# WaldoRevd.net
KiCad netlist of a schematic drawn in EAGLE
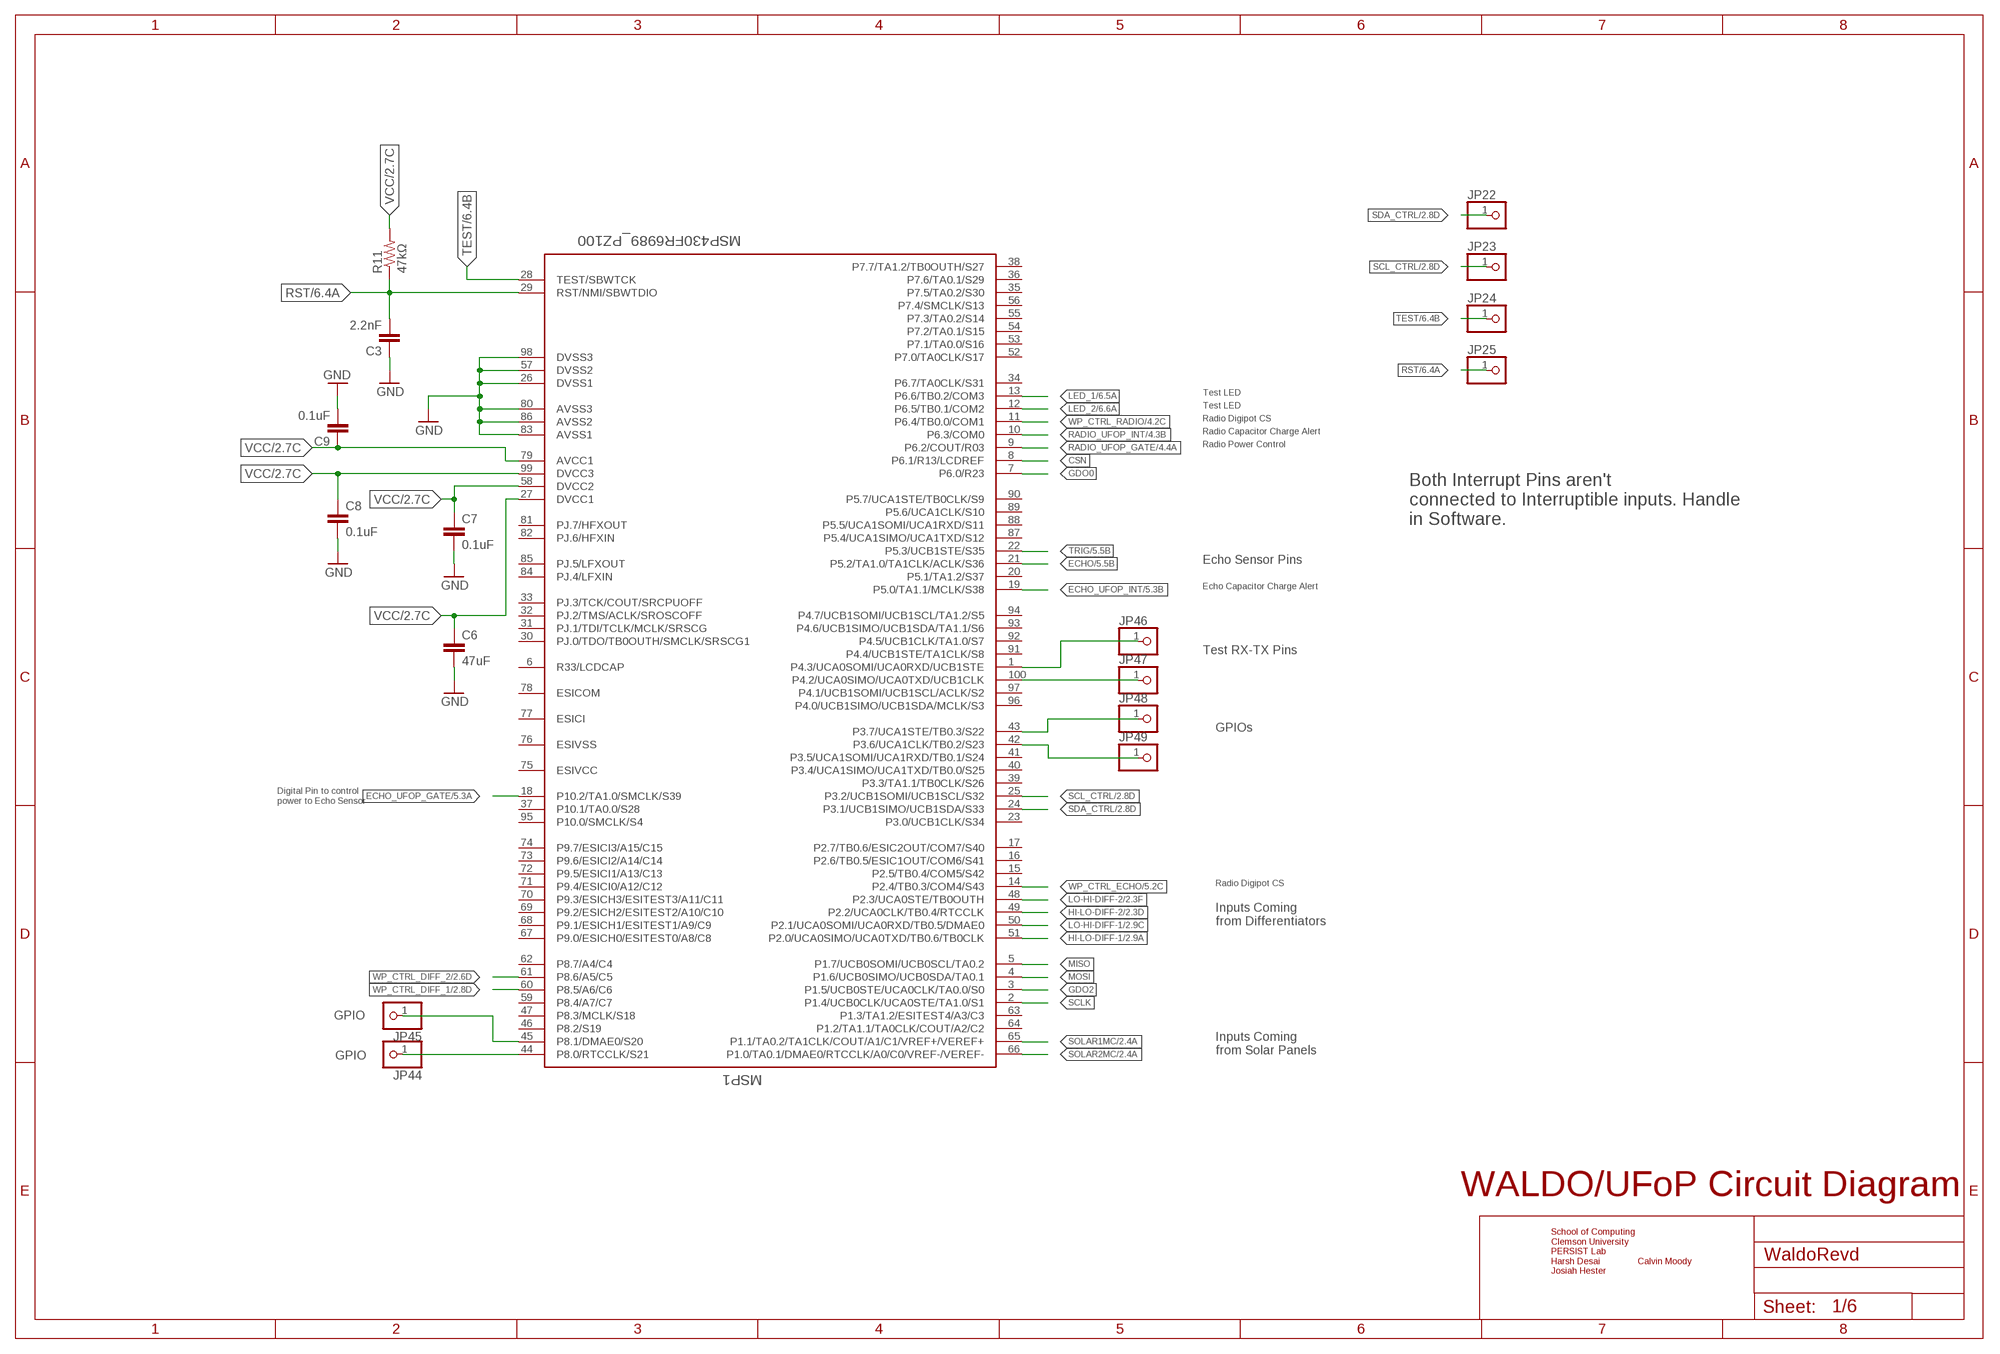
[diagram p0: schematic, sheet 1]
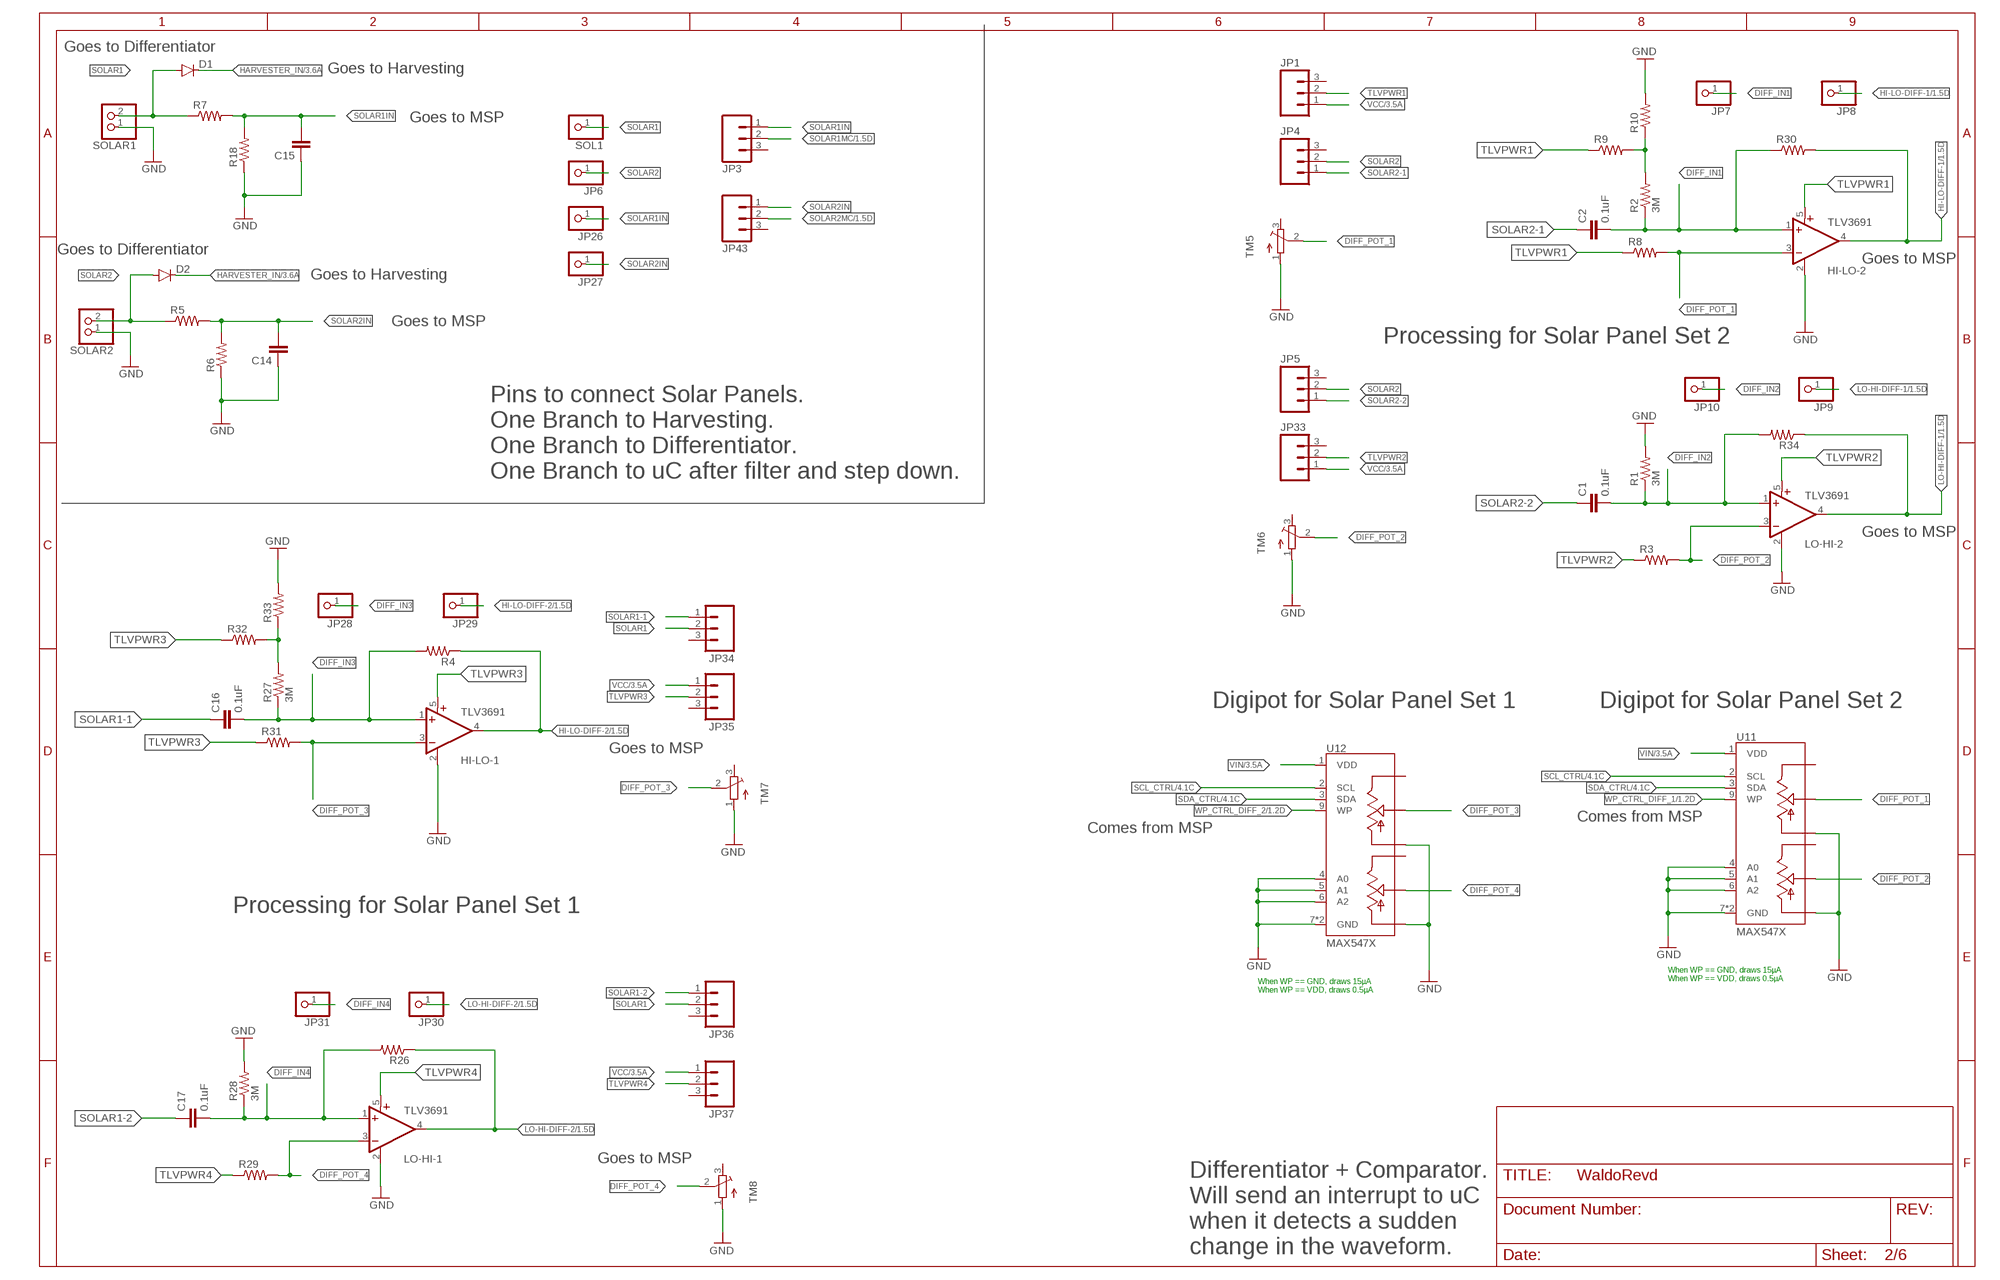
[diagram p1: schematic, sheet 2]
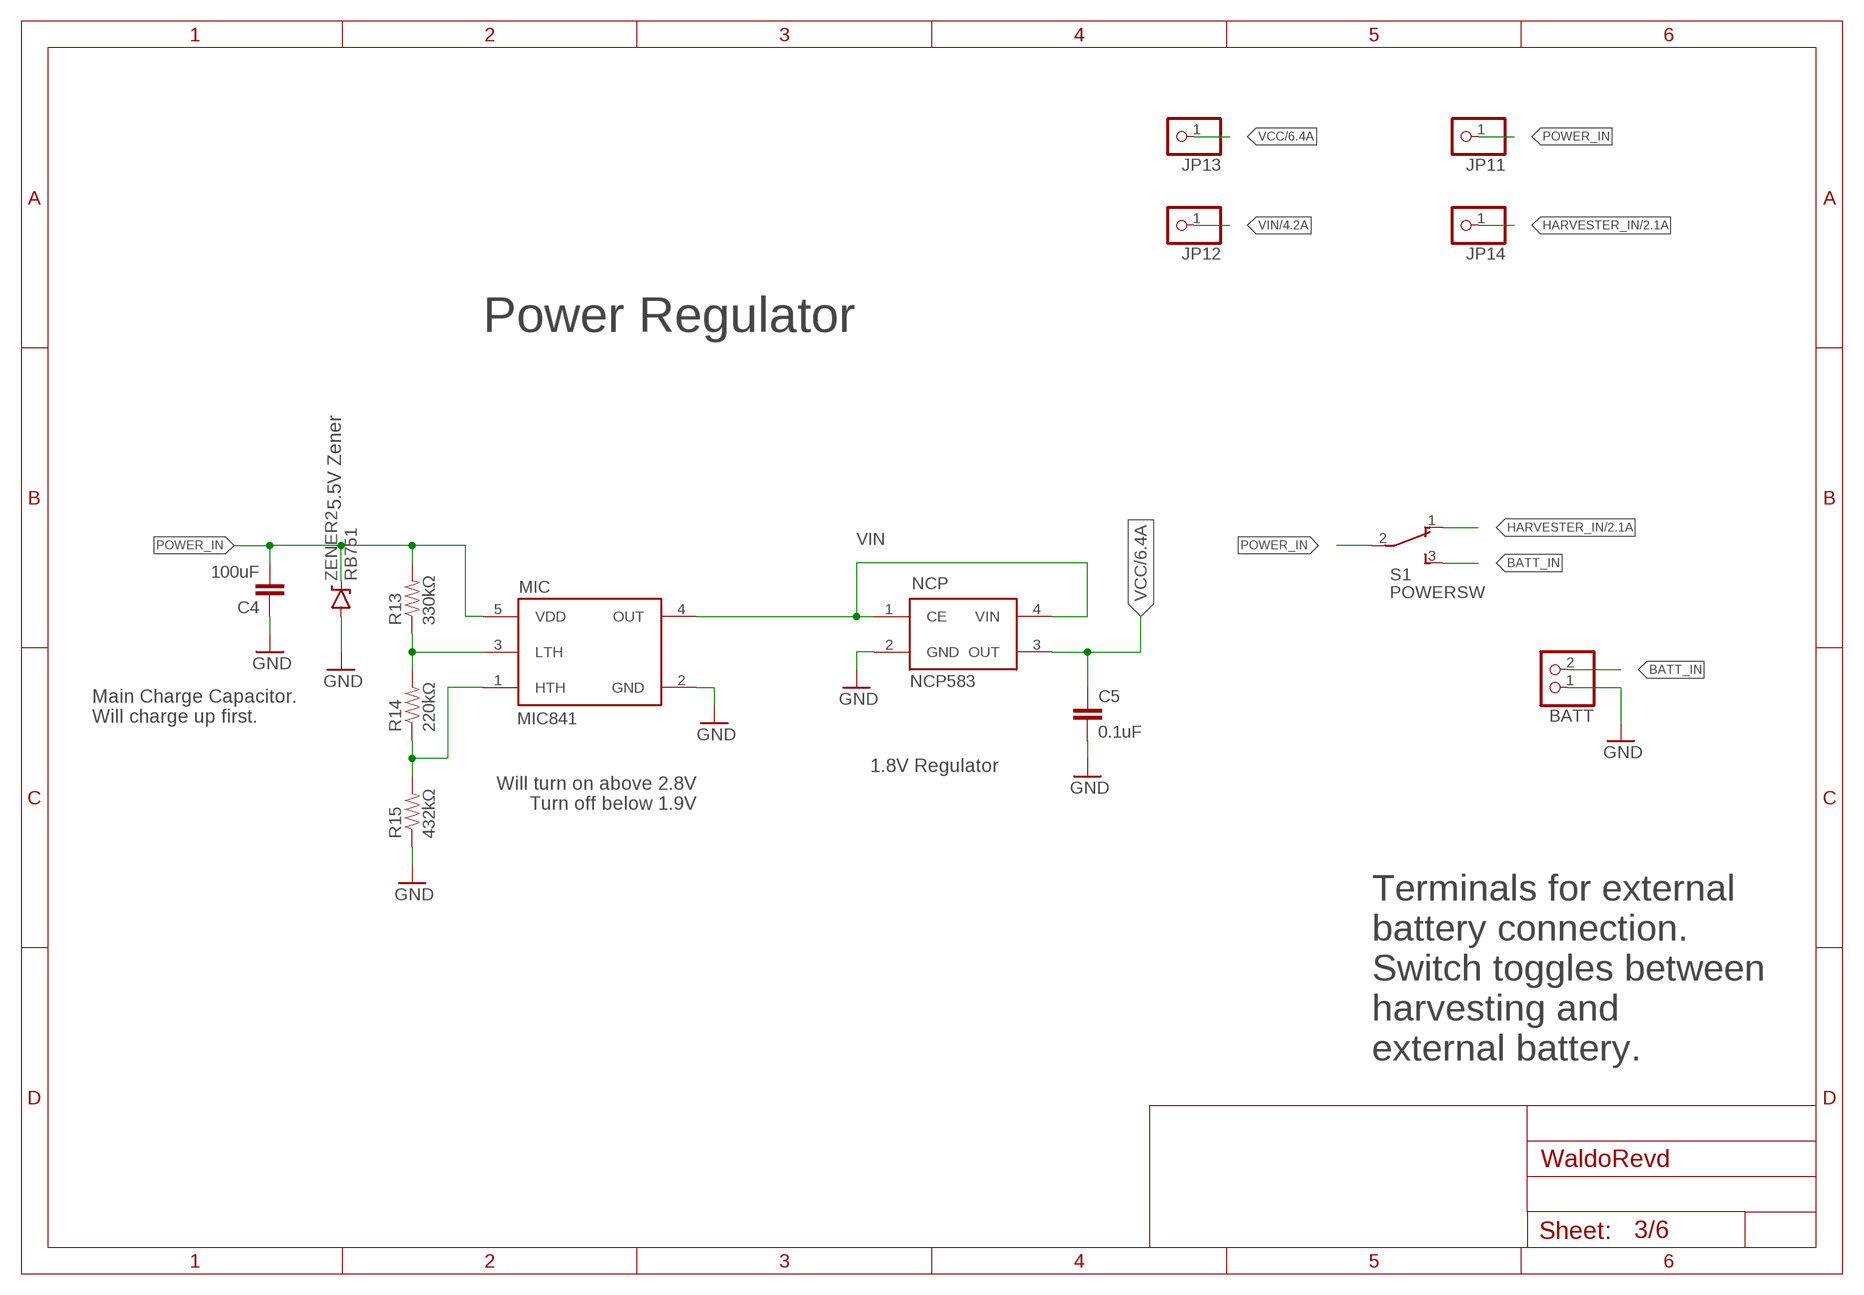
[diagram p2: schematic, sheet 3]
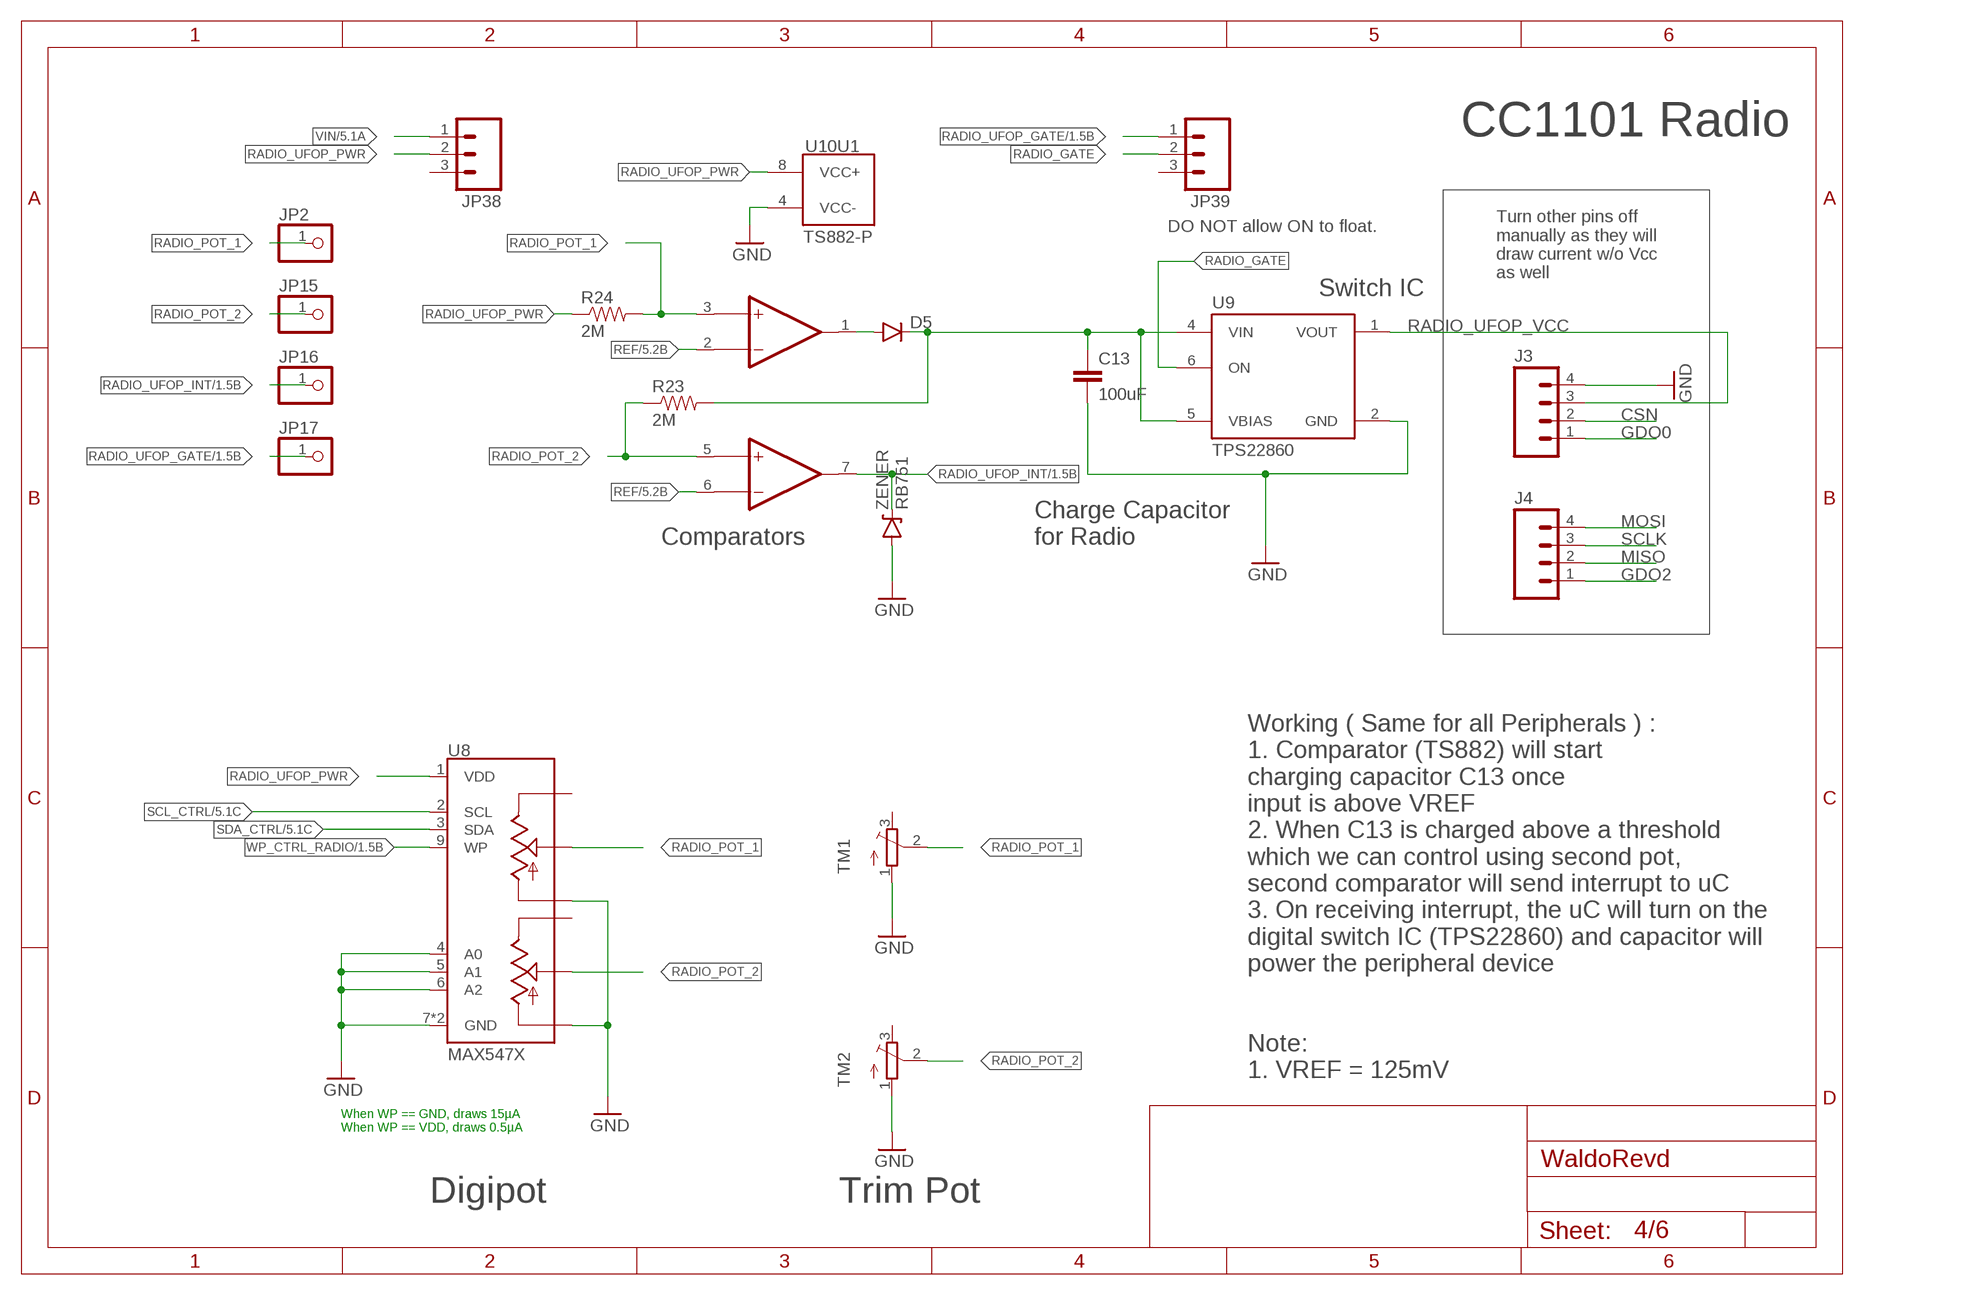
[diagram p3: schematic, sheet 4]
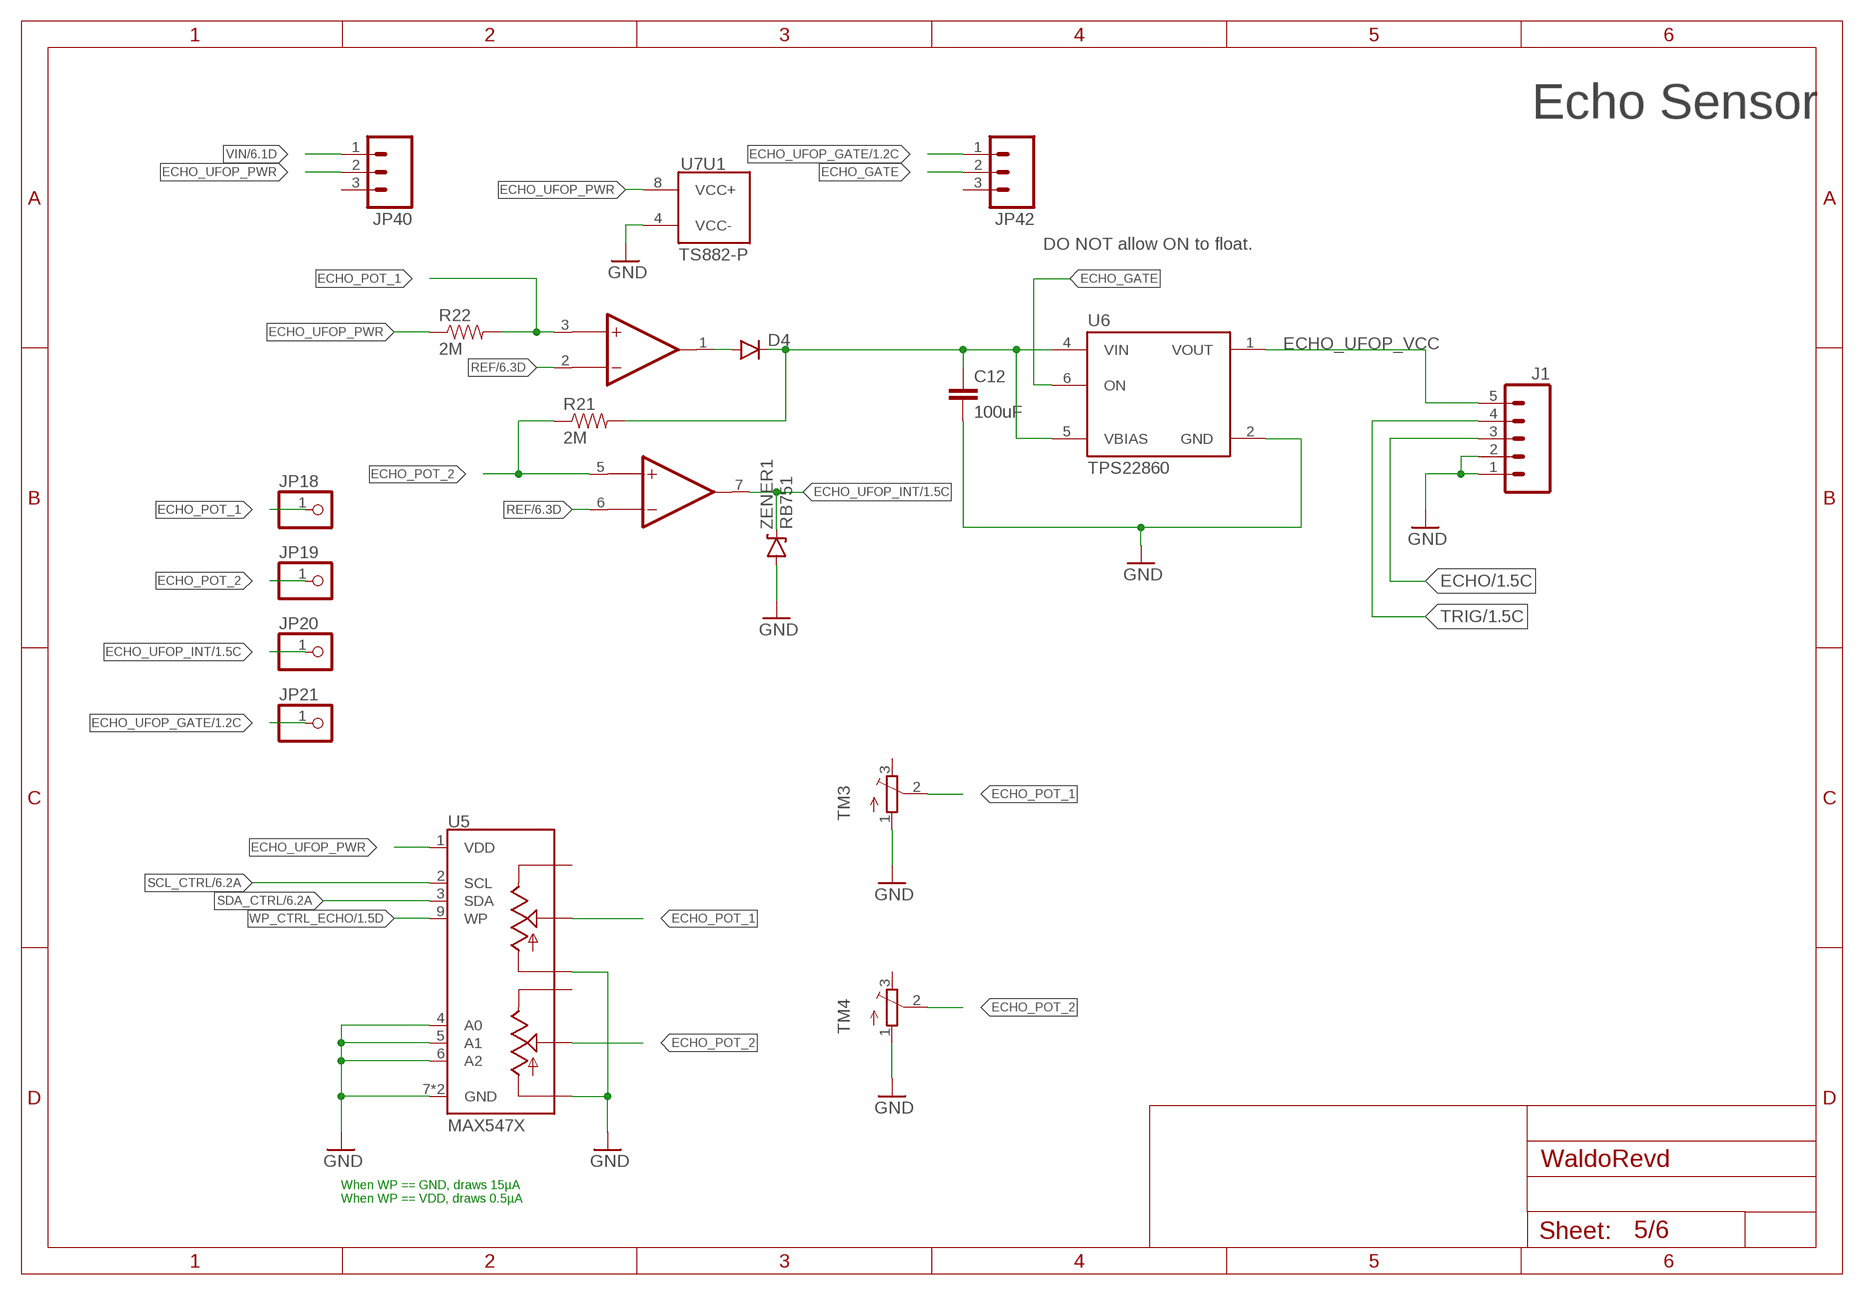
[diagram p4: schematic, sheet 5]
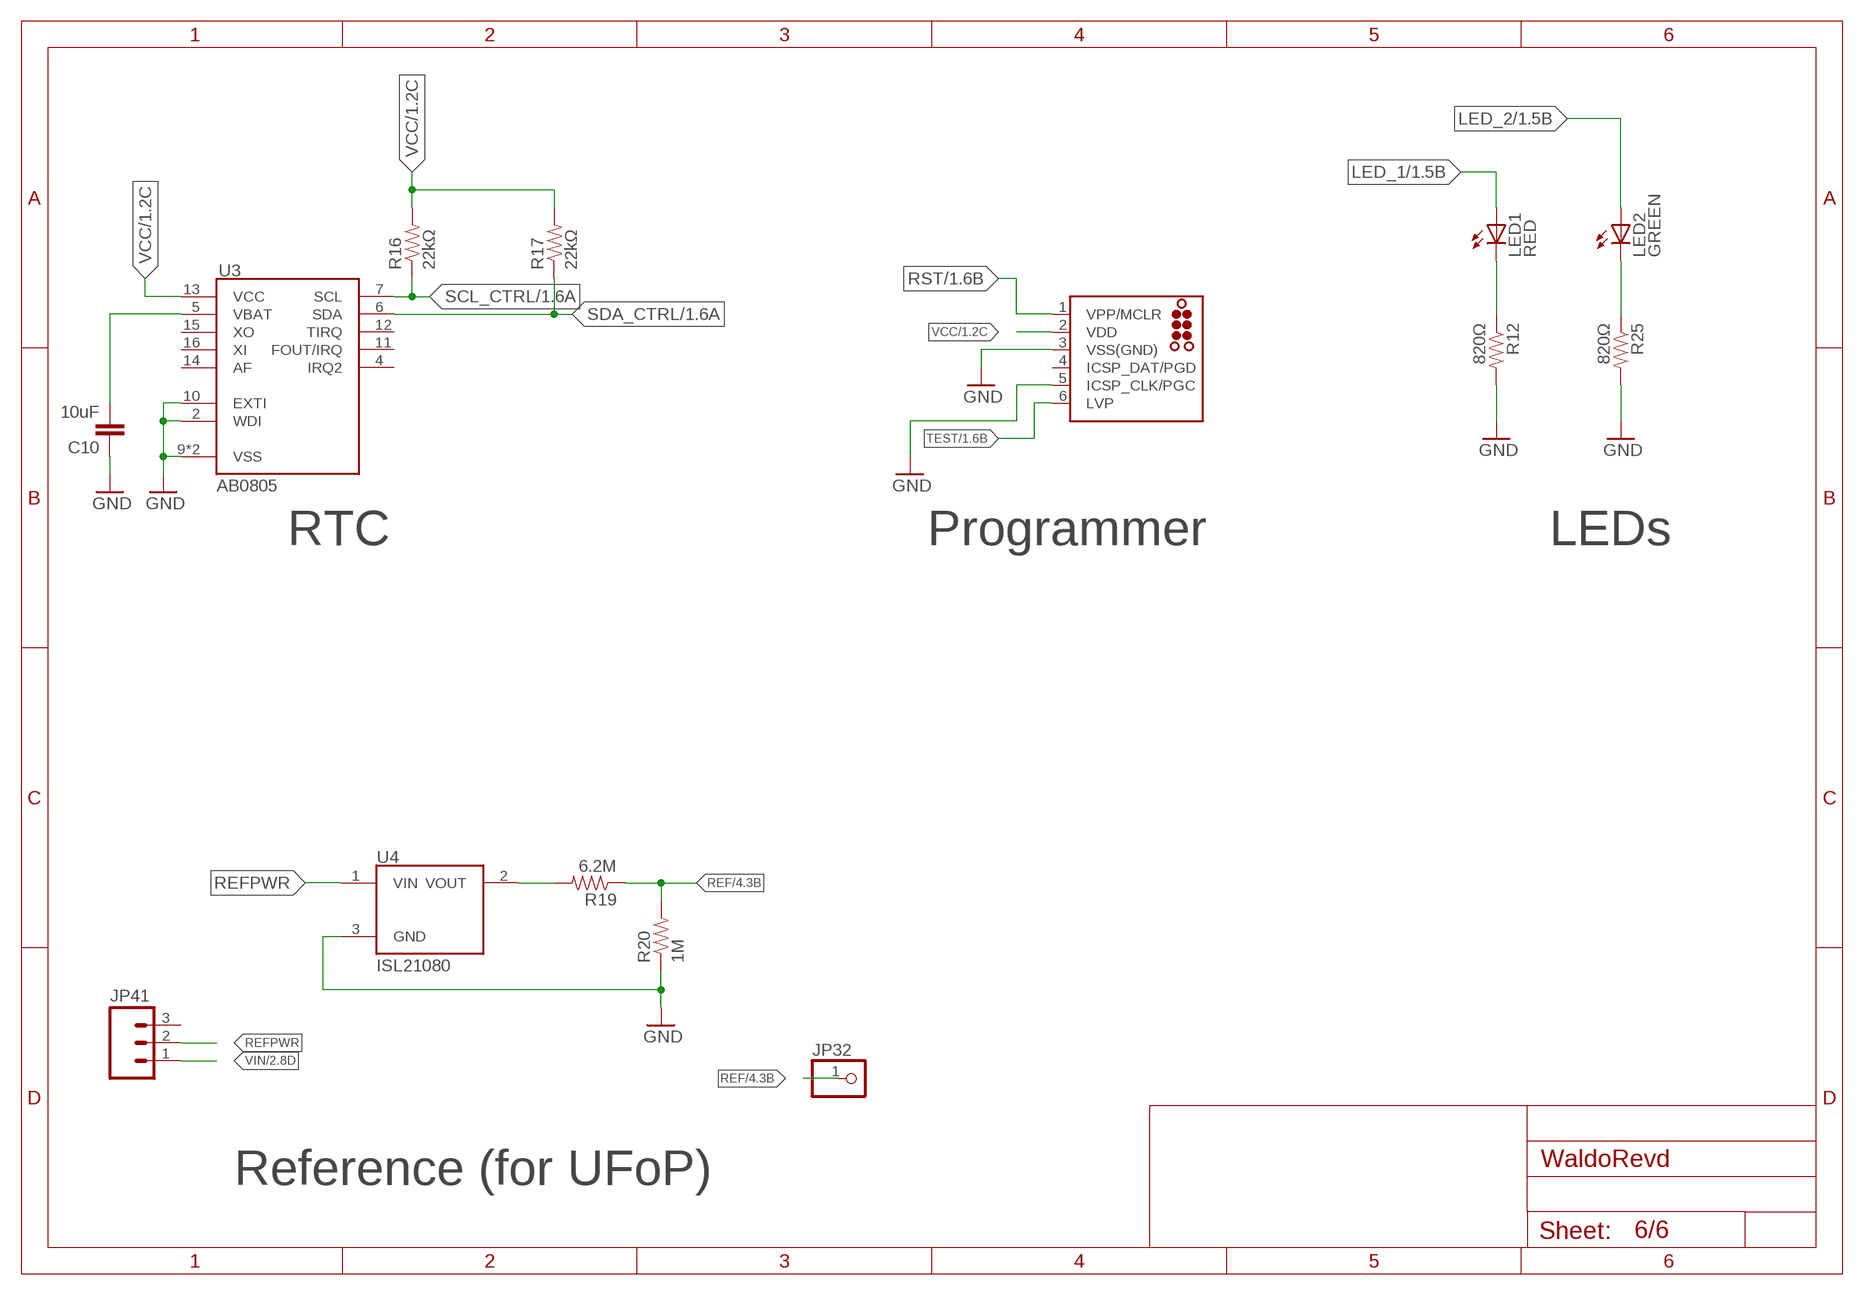
[diagram p5: schematic, sheet 6]

(export (version "E")
  (design (tool "Eeschema 10.0.6"))
  (components
    (comp (ref "C12")
      (value "100uF")
      (footprint "eagle-import:0805")
      (libsource (lib "eagle-import") (part "CAP0805"))
    )
    (comp (ref "D4")
      (value "DIODESOD523")
      (footprint "eagle-import:SOD523")
      (libsource (lib "eagle-import") (part "DIODESOD523"))
    )
    (comp (ref "J1")
      (value "M05PTH")
      (footprint "eagle-import:1X05")
      (libsource (lib "eagle-import") (part "M05PTH"))
    )
    (comp (ref "JP18")
      (value "PINHD-1X1")
      (footprint "eagle-import:1X01")
      (libsource (lib "eagle-import") (part "PINHD-1X1"))
    )
    (comp (ref "JP19")
      (value "PINHD-1X1")
      (footprint "eagle-import:1X01")
      (libsource (lib "eagle-import") (part "PINHD-1X1"))
    )
    (comp (ref "JP20")
      (value "PINHD-1X1")
      (footprint "eagle-import:1X01")
      (libsource (lib "eagle-import") (part "PINHD-1X1"))
    )
    (comp (ref "JP21")
      (value "PINHD-1X1")
      (footprint "eagle-import:1X01")
      (libsource (lib "eagle-import") (part "PINHD-1X1"))
    )
    (comp (ref "JP40")
      (value "M03")
      (footprint "eagle-import:1X03-1.27MM")
      (libsource (lib "eagle-import") (part "M03"))
    )
    (comp (ref "JP42")
      (value "M03")
      (footprint "eagle-import:1X03-1.27MM")
      (libsource (lib "eagle-import") (part "M03"))
    )
    (comp (ref "R21")
      (value "2M")
      (footprint "eagle-import:0805")
      (libsource (lib "eagle-import") (part "RESISTOR0805-RES"))
    )
    (comp (ref "R22")
      (value "2M")
      (footprint "eagle-import:0805")
      (libsource (lib "eagle-import") (part "RESISTOR0805-RES"))
    )
    (comp (ref "TM3")
      (value "TRIMPOTTC33X")
      (footprint "eagle-import:TC33X")
      (libsource (lib "eagle-import") (part "TRIMPOTTC33X"))
    )
    (comp (ref "TM4")
      (value "TRIMPOTTC33X")
      (footprint "eagle-import:TC33X")
      (libsource (lib "eagle-import") (part "TRIMPOTTC33X"))
    )
    (comp (ref "U5")
      (value "MAX547X")
      (footprint "eagle-import:QFN16")
      (libsource (lib "eagle-import") (part "MAX547X"))
    )
    (comp (ref "U6")
      (value "TPS22860")
      (footprint "eagle-import:TSOT23-6")
      (libsource (lib "eagle-import") (part "TPS22860"))
    )
    (comp (ref "U7")
      (value "TS882-P")
      (footprint "eagle-import:UDFN8")
      (fields (field (name "DIGIKEY") "497-14073-1-ND"))
      (libsource (lib "eagle-import") (part "TS882-P"))
    )
    (comp (ref "ZENER1")
      (value "RB751")
      (footprint "eagle-import:SOD-523")
      (libsource (lib "eagle-import") (part "DIODE-ZENER"))
    )
    (comp (ref "C13")
      (value "100uF")
      (footprint "eagle-import:0805")
      (libsource (lib "eagle-import") (part "CAP0805"))
    )
    (comp (ref "D5")
      (value "DIODESOD523")
      (footprint "eagle-import:SOD523")
      (libsource (lib "eagle-import") (part "DIODESOD523"))
    )
    (comp (ref "J3")
      (value "M04PTH")
      (footprint "eagle-import:1X04")
      (libsource (lib "eagle-import") (part "M04PTH"))
    )
    (comp (ref "J4")
      (value "M04PTH")
      (footprint "eagle-import:1X04")
      (libsource (lib "eagle-import") (part "M04PTH"))
    )
    (comp (ref "JP2")
      (value "PINHD-1X1")
      (footprint "eagle-import:1X01")
      (libsource (lib "eagle-import") (part "PINHD-1X1"))
    )
    (comp (ref "JP15")
      (value "PINHD-1X1")
      (footprint "eagle-import:1X01")
      (libsource (lib "eagle-import") (part "PINHD-1X1"))
    )
    (comp (ref "JP16")
      (value "PINHD-1X1")
      (footprint "eagle-import:1X01")
      (libsource (lib "eagle-import") (part "PINHD-1X1"))
    )
    (comp (ref "JP17")
      (value "PINHD-1X1")
      (footprint "eagle-import:1X01")
      (libsource (lib "eagle-import") (part "PINHD-1X1"))
    )
    (comp (ref "JP38")
      (value "M03")
      (footprint "eagle-import:1X03-1.27MM")
      (libsource (lib "eagle-import") (part "M03"))
    )
    (comp (ref "JP39")
      (value "M03")
      (footprint "eagle-import:1X03-1.27MM")
      (libsource (lib "eagle-import") (part "M03"))
    )
    (comp (ref "R23")
      (value "2M")
      (footprint "eagle-import:0805")
      (libsource (lib "eagle-import") (part "RESISTOR0805-RES"))
    )
    (comp (ref "R24")
      (value "2M")
      (footprint "eagle-import:0805")
      (libsource (lib "eagle-import") (part "RESISTOR0805-RES"))
    )
    (comp (ref "TM1")
      (value "TRIMPOTTC33X")
      (footprint "eagle-import:TC33X")
      (libsource (lib "eagle-import") (part "TRIMPOTTC33X"))
    )
    (comp (ref "TM2")
      (value "TRIMPOTTC33X")
      (footprint "eagle-import:TC33X")
      (libsource (lib "eagle-import") (part "TRIMPOTTC33X"))
    )
    (comp (ref "U8")
      (value "MAX547X")
      (footprint "eagle-import:QFN16")
      (libsource (lib "eagle-import") (part "MAX547X"))
    )
    (comp (ref "U9")
      (value "TPS22860")
      (footprint "eagle-import:TSOT23-6")
      (libsource (lib "eagle-import") (part "TPS22860"))
    )
    (comp (ref "U10")
      (value "TS882-P")
      (footprint "eagle-import:UDFN8")
      (fields (field (name "DIGIKEY") "497-14073-1-ND"))
      (libsource (lib "eagle-import") (part "TS882-P"))
    )
    (comp (ref "ZENER")
      (value "RB751")
      (footprint "eagle-import:SOD-523")
      (libsource (lib "eagle-import") (part "DIODE-ZENER"))
    )
    (comp (ref "C3")
      (value "2.2nF")
      (footprint "eagle-import:0805")
      (libsource (lib "eagle-import") (part "CAP0805"))
    )
    (comp (ref "C6")
      (value "47uF")
      (footprint "eagle-import:0805")
      (libsource (lib "eagle-import") (part "CAP0805"))
    )
    (comp (ref "C7")
      (value "0.1uF")
      (footprint "eagle-import:0805")
      (libsource (lib "eagle-import") (part "CAP0805"))
    )
    (comp (ref "C8")
      (value "0.1uF")
      (footprint "eagle-import:0805")
      (libsource (lib "eagle-import") (part "CAP0805"))
    )
    (comp (ref "C9")
      (value "0.1uF")
      (footprint "eagle-import:0805")
      (libsource (lib "eagle-import") (part "CAP0805"))
    )
    (comp (ref "JP22")
      (value "PINHD-1X1")
      (footprint "eagle-import:1X01")
      (libsource (lib "eagle-import") (part "PINHD-1X1"))
    )
    (comp (ref "JP23")
      (value "PINHD-1X1")
      (footprint "eagle-import:1X01")
      (libsource (lib "eagle-import") (part "PINHD-1X1"))
    )
    (comp (ref "JP24")
      (value "PINHD-1X1")
      (footprint "eagle-import:1X01")
      (libsource (lib "eagle-import") (part "PINHD-1X1"))
    )
    (comp (ref "JP25")
      (value "PINHD-1X1")
      (footprint "eagle-import:1X01")
      (libsource (lib "eagle-import") (part "PINHD-1X1"))
    )
    (comp (ref "JP44")
      (value "PINHD-1X1")
      (footprint "eagle-import:1X01")
      (libsource (lib "eagle-import") (part "PINHD-1X1"))
    )
    (comp (ref "JP45")
      (value "PINHD-1X1")
      (footprint "eagle-import:1X01")
      (libsource (lib "eagle-import") (part "PINHD-1X1"))
    )
    (comp (ref "JP46")
      (value "PINHD-1X1")
      (footprint "eagle-import:1X01")
      (libsource (lib "eagle-import") (part "PINHD-1X1"))
    )
    (comp (ref "JP47")
      (value "PINHD-1X1")
      (footprint "eagle-import:1X01")
      (libsource (lib "eagle-import") (part "PINHD-1X1"))
    )
    (comp (ref "JP48")
      (value "PINHD-1X1")
      (footprint "eagle-import:1X01")
      (libsource (lib "eagle-import") (part "PINHD-1X1"))
    )
    (comp (ref "JP49")
      (value "PINHD-1X1")
      (footprint "eagle-import:1X01")
      (libsource (lib "eagle-import") (part "PINHD-1X1"))
    )
    (comp (ref "MSP1")
      (value "MSP430FR6989_PZ100")
      (footprint "eagle-import:PZ100")
      (libsource (lib "eagle-import") (part "MSP430FR6989_PZ100"))
    )
    (comp (ref "R11")
      (value "47kΩ")
      (footprint "eagle-import:0805")
      (libsource (lib "eagle-import") (part "RESISTOR0805-RES"))
    )
    (comp (ref "C10")
      (value "10uF")
      (footprint "eagle-import:0805")
      (libsource (lib "eagle-import") (part "CAP0805"))
    )
    (comp (ref "J2")
      (value "TC2030-MCP-NL")
      (footprint "eagle-import:TC2030-MCP-NL")
      (libsource (lib "eagle-import") (part "TC2030-MCP-NL"))
    )
    (comp (ref "JP32")
      (value "PINHD-1X1")
      (footprint "eagle-import:1X01")
      (libsource (lib "eagle-import") (part "PINHD-1X1"))
    )
    (comp (ref "JP41")
      (value "M03")
      (footprint "eagle-import:1X03-1.27MM")
      (libsource (lib "eagle-import") (part "M03"))
    )
    (comp (ref "LED1")
      (value "RED")
      (footprint "eagle-import:CHIP-LED0805")
      (libsource (lib "eagle-import") (part "LEDCHIP-LED0805"))
    )
    (comp (ref "LED2")
      (value "GREEN")
      (footprint "eagle-import:CHIP-LED0805")
      (libsource (lib "eagle-import") (part "LEDCHIP-LED0805"))
    )
    (comp (ref "R12")
      (value "820Ω")
      (footprint "eagle-import:0805")
      (libsource (lib "eagle-import") (part "RESISTOR0805-RES"))
    )
    (comp (ref "R16")
      (value "22kΩ")
      (footprint "eagle-import:0805")
      (libsource (lib "eagle-import") (part "RESISTOR0805-RES"))
    )
    (comp (ref "R17")
      (value "22kΩ")
      (footprint "eagle-import:0805")
      (libsource (lib "eagle-import") (part "RESISTOR0805-RES"))
    )
    (comp (ref "R19")
      (value "6.2M")
      (footprint "eagle-import:0805")
      (libsource (lib "eagle-import") (part "RESISTOR0805-RES"))
    )
    (comp (ref "R20")
      (value "1M")
      (footprint "eagle-import:0805")
      (libsource (lib "eagle-import") (part "RESISTOR0805-RES"))
    )
    (comp (ref "R25")
      (value "820Ω")
      (footprint "eagle-import:0805")
      (libsource (lib "eagle-import") (part "RESISTOR0805-RES"))
    )
    (comp (ref "U3")
      (value "AB0805")
      (footprint "eagle-import:QFN16")
      (libsource (lib "eagle-import") (part "AB0805"))
    )
    (comp (ref "U4")
      (value "ISL21080")
      (footprint "eagle-import:SOT-23")
      (libsource (lib "eagle-import") (part "ISL21080"))
    )
    (comp (ref "C1")
      (value "0.1uF")
      (footprint "eagle-import:0805")
      (libsource (lib "eagle-import") (part "CAP0805"))
    )
    (comp (ref "C2")
      (value "0.1uF")
      (footprint "eagle-import:0805")
      (libsource (lib "eagle-import") (part "CAP0805"))
    )
    (comp (ref "C14")
      (value "CAP0805")
      (footprint "eagle-import:0805")
      (libsource (lib "eagle-import") (part "CAP0805"))
    )
    (comp (ref "C15")
      (value "CAP0805")
      (footprint "eagle-import:0805")
      (libsource (lib "eagle-import") (part "CAP0805"))
    )
    (comp (ref "C16")
      (value "0.1uF")
      (footprint "eagle-import:0805")
      (libsource (lib "eagle-import") (part "CAP0805"))
    )
    (comp (ref "C17")
      (value "0.1uF")
      (footprint "eagle-import:0805")
      (libsource (lib "eagle-import") (part "CAP0805"))
    )
    (comp (ref "D1")
      (value "DIODESOD523")
      (footprint "eagle-import:SOD523")
      (libsource (lib "eagle-import") (part "DIODESOD523"))
    )
    (comp (ref "D2")
      (value "DIODESOD523")
      (footprint "eagle-import:SOD523")
      (libsource (lib "eagle-import") (part "DIODESOD523"))
    )
    (comp (ref "HI-LO-1")
      (value "TLV3691")
      (footprint "eagle-import:SC70-5")
      (libsource (lib "eagle-import") (part "TLV3691"))
    )
    (comp (ref "HI-LO-2")
      (value "TLV3691")
      (footprint "eagle-import:SC70-5")
      (libsource (lib "eagle-import") (part "TLV3691"))
    )
    (comp (ref "JP1")
      (value "M03")
      (footprint "eagle-import:1X03-1.27MM")
      (libsource (lib "eagle-import") (part "M03"))
    )
    (comp (ref "JP3")
      (value "M03")
      (footprint "eagle-import:1X03-1.27MM")
      (libsource (lib "eagle-import") (part "M03"))
    )
    (comp (ref "JP4")
      (value "M03")
      (footprint "eagle-import:1X03-1.27MM")
      (libsource (lib "eagle-import") (part "M03"))
    )
    (comp (ref "JP5")
      (value "M03")
      (footprint "eagle-import:1X03-1.27MM")
      (libsource (lib "eagle-import") (part "M03"))
    )
    (comp (ref "JP6")
      (value "PINHD-1X1")
      (footprint "eagle-import:1X01")
      (libsource (lib "eagle-import") (part "PINHD-1X1"))
    )
    (comp (ref "JP7")
      (value "PINHD-1X1")
      (footprint "eagle-import:1X01")
      (libsource (lib "eagle-import") (part "PINHD-1X1"))
    )
    (comp (ref "JP8")
      (value "PINHD-1X1")
      (footprint "eagle-import:1X01")
      (libsource (lib "eagle-import") (part "PINHD-1X1"))
    )
    (comp (ref "JP9")
      (value "PINHD-1X1")
      (footprint "eagle-import:1X01")
      (libsource (lib "eagle-import") (part "PINHD-1X1"))
    )
    (comp (ref "JP10")
      (value "PINHD-1X1")
      (footprint "eagle-import:1X01")
      (libsource (lib "eagle-import") (part "PINHD-1X1"))
    )
    (comp (ref "JP26")
      (value "PINHD-1X1")
      (footprint "eagle-import:1X01")
      (libsource (lib "eagle-import") (part "PINHD-1X1"))
    )
    (comp (ref "JP27")
      (value "PINHD-1X1")
      (footprint "eagle-import:1X01")
      (libsource (lib "eagle-import") (part "PINHD-1X1"))
    )
    (comp (ref "JP28")
      (value "PINHD-1X1")
      (footprint "eagle-import:1X01")
      (libsource (lib "eagle-import") (part "PINHD-1X1"))
    )
    (comp (ref "JP29")
      (value "PINHD-1X1")
      (footprint "eagle-import:1X01")
      (libsource (lib "eagle-import") (part "PINHD-1X1"))
    )
    (comp (ref "JP30")
      (value "PINHD-1X1")
      (footprint "eagle-import:1X01")
      (libsource (lib "eagle-import") (part "PINHD-1X1"))
    )
    (comp (ref "JP31")
      (value "PINHD-1X1")
      (footprint "eagle-import:1X01")
      (libsource (lib "eagle-import") (part "PINHD-1X1"))
    )
    (comp (ref "JP33")
      (value "M03")
      (footprint "eagle-import:1X03-1.27MM")
      (libsource (lib "eagle-import") (part "M03"))
    )
    (comp (ref "JP34")
      (value "M03")
      (footprint "eagle-import:1X03-1.27MM")
      (libsource (lib "eagle-import") (part "M03"))
    )
    (comp (ref "JP35")
      (value "M03")
      (footprint "eagle-import:1X03-1.27MM")
      (libsource (lib "eagle-import") (part "M03"))
    )
    (comp (ref "JP36")
      (value "M03")
      (footprint "eagle-import:1X03-1.27MM")
      (libsource (lib "eagle-import") (part "M03"))
    )
    (comp (ref "JP37")
      (value "M03")
      (footprint "eagle-import:1X03-1.27MM")
      (libsource (lib "eagle-import") (part "M03"))
    )
    (comp (ref "JP43")
      (value "M03")
      (footprint "eagle-import:1X03-1.27MM")
      (libsource (lib "eagle-import") (part "M03"))
    )
    (comp (ref "LO-HI-1")
      (value "TLV3691")
      (footprint "eagle-import:SC70-5")
      (libsource (lib "eagle-import") (part "TLV3691"))
    )
    (comp (ref "LO-HI-2")
      (value "TLV3691")
      (footprint "eagle-import:SC70-5")
      (libsource (lib "eagle-import") (part "TLV3691"))
    )
    (comp (ref "R1")
      (value "3M")
      (footprint "eagle-import:0805")
      (libsource (lib "eagle-import") (part "RESISTOR0805-RES"))
    )
    (comp (ref "R2")
      (value "3M")
      (footprint "eagle-import:0805")
      (libsource (lib "eagle-import") (part "RESISTOR0805-RES"))
    )
    (comp (ref "R3")
      (value "RESISTOR0805-RES")
      (footprint "eagle-import:0805")
      (libsource (lib "eagle-import") (part "RESISTOR0805-RES"))
    )
    (comp (ref "R4")
      (value "RESISTOR0805-RES")
      (footprint "eagle-import:0805")
      (libsource (lib "eagle-import") (part "RESISTOR0805-RES"))
    )
    (comp (ref "R5")
      (value "RESISTOR0805-RES")
      (footprint "eagle-import:0805")
      (libsource (lib "eagle-import") (part "RESISTOR0805-RES"))
    )
    (comp (ref "R6")
      (value "RESISTOR0805-RES")
      (footprint "eagle-import:0805")
      (libsource (lib "eagle-import") (part "RESISTOR0805-RES"))
    )
    (comp (ref "R7")
      (value "RESISTOR0805-RES")
      (footprint "eagle-import:0805")
      (libsource (lib "eagle-import") (part "RESISTOR0805-RES"))
    )
    (comp (ref "R8")
      (value "RESISTOR0805-RES")
      (footprint "eagle-import:0805")
      (libsource (lib "eagle-import") (part "RESISTOR0805-RES"))
    )
    (comp (ref "R9")
      (value "RESISTOR0805-RES")
      (footprint "eagle-import:0805")
      (libsource (lib "eagle-import") (part "RESISTOR0805-RES"))
    )
    (comp (ref "R10")
      (value "RESISTOR0805-RES")
      (footprint "eagle-import:0805")
      (libsource (lib "eagle-import") (part "RESISTOR0805-RES"))
    )
    (comp (ref "R18")
      (value "RESISTOR0805-RES")
      (footprint "eagle-import:0805")
      (libsource (lib "eagle-import") (part "RESISTOR0805-RES"))
    )
    (comp (ref "R26")
      (value "RESISTOR0805-RES")
      (footprint "eagle-import:0805")
      (libsource (lib "eagle-import") (part "RESISTOR0805-RES"))
    )
    (comp (ref "R27")
      (value "3M")
      (footprint "eagle-import:0805")
      (libsource (lib "eagle-import") (part "RESISTOR0805-RES"))
    )
    (comp (ref "R28")
      (value "3M")
      (footprint "eagle-import:0805")
      (libsource (lib "eagle-import") (part "RESISTOR0805-RES"))
    )
    (comp (ref "R29")
      (value "RESISTOR0805-RES")
      (footprint "eagle-import:0805")
      (libsource (lib "eagle-import") (part "RESISTOR0805-RES"))
    )
    (comp (ref "R30")
      (value "RESISTOR0805-RES")
      (footprint "eagle-import:0805")
      (libsource (lib "eagle-import") (part "RESISTOR0805-RES"))
    )
    (comp (ref "R31")
      (value "RESISTOR0805-RES")
      (footprint "eagle-import:0805")
      (libsource (lib "eagle-import") (part "RESISTOR0805-RES"))
    )
    (comp (ref "R32")
      (value "RESISTOR0805-RES")
      (footprint "eagle-import:0805")
      (libsource (lib "eagle-import") (part "RESISTOR0805-RES"))
    )
    (comp (ref "R33")
      (value "RESISTOR0805-RES")
      (footprint "eagle-import:0805")
      (libsource (lib "eagle-import") (part "RESISTOR0805-RES"))
    )
    (comp (ref "R34")
      (value "RESISTOR0805-RES")
      (footprint "eagle-import:0805")
      (libsource (lib "eagle-import") (part "RESISTOR0805-RES"))
    )
    (comp (ref "SOL1")
      (value "PINHD-1X1")
      (footprint "eagle-import:1X01")
      (libsource (lib "eagle-import") (part "PINHD-1X1"))
    )
    (comp (ref "SOLAR1")
      (value "PINHD-1X2")
      (footprint "eagle-import:1X02")
      (libsource (lib "eagle-import") (part "PINHD-1X2"))
    )
    (comp (ref "SOLAR2")
      (value "PINHD-1X2")
      (footprint "eagle-import:1X02")
      (libsource (lib "eagle-import") (part "PINHD-1X2"))
    )
    (comp (ref "TM5")
      (value "TRIMPOTTC33X")
      (footprint "eagle-import:TC33X")
      (libsource (lib "eagle-import") (part "TRIMPOTTC33X"))
    )
    (comp (ref "TM6")
      (value "TRIMPOTTC33X")
      (footprint "eagle-import:TC33X")
      (libsource (lib "eagle-import") (part "TRIMPOTTC33X"))
    )
    (comp (ref "TM7")
      (value "TRIMPOTTC33X")
      (footprint "eagle-import:TC33X")
      (libsource (lib "eagle-import") (part "TRIMPOTTC33X"))
    )
    (comp (ref "TM8")
      (value "TRIMPOTTC33X")
      (footprint "eagle-import:TC33X")
      (libsource (lib "eagle-import") (part "TRIMPOTTC33X"))
    )
    (comp (ref "U11")
      (value "MAX547X")
      (footprint "eagle-import:QFN16")
      (libsource (lib "eagle-import") (part "MAX547X"))
    )
    (comp (ref "U12")
      (value "MAX547X")
      (footprint "eagle-import:QFN16")
      (libsource (lib "eagle-import") (part "MAX547X"))
    )
    (comp (ref "BATT")
      (value "PINHD-1X2")
      (footprint "eagle-import:1X02")
      (libsource (lib "eagle-import") (part "PINHD-1X2"))
    )
    (comp (ref "C4")
      (value "100uF")
      (footprint "eagle-import:0805")
      (libsource (lib "eagle-import") (part "CAP0805"))
    )
    (comp (ref "C5")
      (value "0.1uF")
      (footprint "eagle-import:0805")
      (libsource (lib "eagle-import") (part "CAP0805"))
    )
    (comp (ref "JP11")
      (value "PINHD-1X1")
      (footprint "eagle-import:1X01")
      (libsource (lib "eagle-import") (part "PINHD-1X1"))
    )
    (comp (ref "JP12")
      (value "PINHD-1X1")
      (footprint "eagle-import:1X01")
      (libsource (lib "eagle-import") (part "PINHD-1X1"))
    )
    (comp (ref "JP13")
      (value "PINHD-1X1")
      (footprint "eagle-import:1X01")
      (libsource (lib "eagle-import") (part "PINHD-1X1"))
    )
    (comp (ref "JP14")
      (value "PINHD-1X1")
      (footprint "eagle-import:1X01")
      (libsource (lib "eagle-import") (part "PINHD-1X1"))
    )
    (comp (ref "MIC")
      (value "MIC841")
      (footprint "eagle-import:SC70-5")
      (libsource (lib "eagle-import") (part "MIC841"))
    )
    (comp (ref "NCP")
      (value "NCP583")
      (footprint "eagle-import:SC82-AB_1PRIMARY")
      (libsource (lib "eagle-import") (part "NCP583"))
    )
    (comp (ref "R13")
      (value "330kΩ")
      (footprint "eagle-import:0805")
      (libsource (lib "eagle-import") (part "RESISTOR0805-RES"))
    )
    (comp (ref "R14")
      (value "220kΩ")
      (footprint "eagle-import:0805")
      (libsource (lib "eagle-import") (part "RESISTOR0805-RES"))
    )
    (comp (ref "R15")
      (value "432kΩ")
      (footprint "eagle-import:0805")
      (libsource (lib "eagle-import") (part "RESISTOR0805-RES"))
    )
    (comp (ref "S1")
      (value "POWERSW")
      (footprint "eagle-import:TL3XYO")
      (libsource (lib "eagle-import") (part "POWERSW"))
    )
    (comp (ref "ZENER2")
      (value "RB751")
      (footprint "eagle-import:SOD-523")
      (libsource (lib "eagle-import") (part "DIODE-ZENER"))
    )
  )
  (nets
    (net (code "1") (name "BATT_IN") (class "Default")
      (node (ref "BATT") (pin "2") (pinfunction "2_2") (pintype "passive"))
      (node (ref "S1") (pin "3") (pinfunction "S_3") (pintype "passive"))
    )
    (net (code "2") (name "CSN") (class "Default")
      (node (ref "J3") (pin "2") (pinfunction "2_2") (pintype "passive"))
      (node (ref "MSP1") (pin "8") (pinfunction "P6.1/R13/LCDREF_8") (pintype "bidirectional"))
    )
    (net (code "3") (name "DIFF_IN1") (class "Default")
      (node (ref "C2") (pin "2") (pinfunction "2_2") (pintype "passive"))
      (node (ref "HI-LO-2") (pin "1") (pinfunction "+IN_1") (pintype "input"))
      (node (ref "JP7") (pin "1") (pinfunction "1_1") (pintype "passive"))
      (node (ref "R2") (pin "1") (pinfunction "1_1") (pintype "passive"))
      (node (ref "R30") (pin "1") (pinfunction "1_1") (pintype "passive"))
    )
    (net (code "4") (name "DIFF_IN2") (class "Default")
      (node (ref "C1") (pin "2") (pinfunction "2_2") (pintype "passive"))
      (node (ref "JP10") (pin "1") (pinfunction "1_1") (pintype "passive"))
      (node (ref "LO-HI-2") (pin "1") (pinfunction "+IN_1") (pintype "input"))
      (node (ref "R1") (pin "1") (pinfunction "1_1") (pintype "passive"))
      (node (ref "R34") (pin "2") (pinfunction "2_2") (pintype "passive"))
    )
    (net (code "5") (name "DIFF_IN3") (class "Default")
      (node (ref "C16") (pin "2") (pinfunction "2_2") (pintype "passive"))
      (node (ref "HI-LO-1") (pin "1") (pinfunction "+IN_1") (pintype "input"))
      (node (ref "JP28") (pin "1") (pinfunction "1_1") (pintype "passive"))
      (node (ref "R27") (pin "1") (pinfunction "1_1") (pintype "passive"))
      (node (ref "R4") (pin "2") (pinfunction "2_2") (pintype "passive"))
    )
    (net (code "6") (name "DIFF_IN4") (class "Default")
      (node (ref "C17") (pin "2") (pinfunction "2_2") (pintype "passive"))
      (node (ref "JP31") (pin "1") (pinfunction "1_1") (pintype "passive"))
      (node (ref "LO-HI-1") (pin "1") (pinfunction "+IN_1") (pintype "input"))
      (node (ref "R26") (pin "2") (pinfunction "2_2") (pintype "passive"))
      (node (ref "R28") (pin "1") (pinfunction "1_1") (pintype "passive"))
    )
    (net (code "7") (name "DIFF_POT_1") (class "Default")
      (node (ref "HI-LO-2") (pin "3") (pinfunction "-IN_3") (pintype "input"))
      (node (ref "R8") (pin "2") (pinfunction "2_2") (pintype "passive"))
      (node (ref "TM5") (pin "2") (pinfunction "S_2") (pintype "passive"))
      (node (ref "U11") (pin "14") (pinfunction "WA_14") (pintype "passive"))
    )
    (net (code "8") (name "DIFF_POT_2") (class "Default")
      (node (ref "LO-HI-2") (pin "3") (pinfunction "-IN_3") (pintype "input"))
      (node (ref "R3") (pin "2") (pinfunction "2_2") (pintype "passive"))
      (node (ref "TM6") (pin "2") (pinfunction "S_2") (pintype "passive"))
      (node (ref "U11") (pin "11") (pinfunction "WB_11") (pintype "bidirectional"))
    )
    (net (code "9") (name "DIFF_POT_3") (class "Default")
      (node (ref "HI-LO-1") (pin "3") (pinfunction "-IN_3") (pintype "input"))
      (node (ref "R31") (pin "2") (pinfunction "2_2") (pintype "passive"))
      (node (ref "TM7") (pin "2") (pinfunction "S_2") (pintype "passive"))
      (node (ref "U12") (pin "14") (pinfunction "WA_14") (pintype "passive"))
    )
    (net (code "10") (name "DIFF_POT_4") (class "Default")
      (node (ref "LO-HI-1") (pin "3") (pinfunction "-IN_3") (pintype "input"))
      (node (ref "R29") (pin "2") (pinfunction "2_2") (pintype "passive"))
      (node (ref "TM8") (pin "2") (pinfunction "S_2") (pintype "passive"))
      (node (ref "U12") (pin "11") (pinfunction "WB_11") (pintype "bidirectional"))
    )
    (net (code "11") (name "ECHO") (class "Default")
      (node (ref "J1") (pin "3") (pinfunction "3_3") (pintype "passive"))
      (node (ref "MSP1") (pin "21") (pinfunction "P5.2/TA1.0/TA1CLK/ACLK/S36_21") (pintype "bidirectional"))
    )
    (net (code "12") (name "ECHO_GATE") (class "Default")
      (node (ref "JP42") (pin "2") (pinfunction "2_2") (pintype "passive"))
      (node (ref "U6") (pin "6") (pinfunction "ON_6") (pintype "bidirectional"))
    )
    (net (code "13") (name "ECHO_POT_1") (class "Default")
      (node (ref "JP18") (pin "1") (pinfunction "1_1") (pintype "passive"))
      (node (ref "R22") (pin "2") (pinfunction "2_2") (pintype "passive"))
      (node (ref "TM3") (pin "2") (pinfunction "S_2") (pintype "passive"))
      (node (ref "U5") (pin "14") (pinfunction "WA_14") (pintype "passive"))
      (node (ref "U7") (pin "3") (pinfunction "IN1+_3") (pintype "input"))
    )
    (net (code "14") (name "ECHO_POT_2") (class "Default")
      (node (ref "JP19") (pin "1") (pinfunction "1_1") (pintype "passive"))
      (node (ref "R21") (pin "1") (pinfunction "1_1") (pintype "passive"))
      (node (ref "TM4") (pin "2") (pinfunction "S_2") (pintype "passive"))
      (node (ref "U5") (pin "11") (pinfunction "WB_11") (pintype "bidirectional"))
      (node (ref "U7") (pin "5") (pinfunction "IN1+_5") (pintype "input"))
    )
    (net (code "15") (name "ECHO_UFOP_GATE") (class "Default")
      (node (ref "JP21") (pin "1") (pinfunction "1_1") (pintype "passive"))
      (node (ref "JP42") (pin "1") (pinfunction "1_1") (pintype "passive"))
      (node (ref "MSP1") (pin "18") (pinfunction "P10.2/TA1.0/SMCLK/S39_18") (pintype "bidirectional"))
    )
    (net (code "16") (name "ECHO_UFOP_INT") (class "Default")
      (node (ref "JP20") (pin "1") (pinfunction "1_1") (pintype "passive"))
      (node (ref "MSP1") (pin "19") (pinfunction "P5.0/TA1.1/MCLK/S38_19") (pintype "bidirectional"))
      (node (ref "U7") (pin "7") (pinfunction "OUT1_7") (pintype "output"))
      (node (ref "ZENER1") (pin "CATHODE") (pinfunction "C_CATHODE") (pintype "passive"))
    )
    (net (code "17") (name "ECHO_UFOP_PWR") (class "Default")
      (node (ref "JP40") (pin "2") (pinfunction "2_2") (pintype "passive"))
      (node (ref "R22") (pin "1") (pinfunction "1_1") (pintype "passive"))
      (node (ref "U5") (pin "1") (pinfunction "VDD_1") (pintype "bidirectional"))
      (node (ref "U7") (pin "8") (pinfunction "VCC+_8") (pintype "bidirectional"))
    )
    (net (code "18") (name "ECHO_UFOP_VCC") (class "Default")
      (node (ref "J1") (pin "5") (pinfunction "5_5") (pintype "passive"))
      (node (ref "U6") (pin "1") (pinfunction "VOUT_1") (pintype "bidirectional"))
    )
    (net (code "19") (name "GDO0") (class "Default")
      (node (ref "J3") (pin "1") (pinfunction "1_1") (pintype "passive"))
      (node (ref "MSP1") (pin "7") (pinfunction "P6.0/R23_7") (pintype "bidirectional"))
    )
    (net (code "20") (name "GDO2") (class "Default")
      (node (ref "J4") (pin "1") (pinfunction "1_1") (pintype "passive"))
      (node (ref "MSP1") (pin "3") (pinfunction "P1.5/UCB0STE/UCA0CLK/TA0.0/S0_3") (pintype "bidirectional"))
    )
    (net (code "21") (name "GND") (class "Default")
      (node (ref "BATT") (pin "1") (pinfunction "1_1") (pintype "passive"))
      (node (ref "C10") (pin "1") (pinfunction "1_1") (pintype "passive"))
      (node (ref "C12") (pin "2") (pinfunction "2_2") (pintype "passive"))
      (node (ref "C13") (pin "2") (pinfunction "2_2") (pintype "passive"))
      (node (ref "C14") (pin "1") (pinfunction "1_1") (pintype "passive"))
      (node (ref "C15") (pin "1") (pinfunction "1_1") (pintype "passive"))
      (node (ref "C3") (pin "1") (pinfunction "1_1") (pintype "passive"))
      (node (ref "C4") (pin "1") (pinfunction "1_1") (pintype "passive"))
      (node (ref "C5") (pin "2") (pinfunction "2_2") (pintype "passive"))
      (node (ref "C6") (pin "2") (pinfunction "2_2") (pintype "passive"))
      (node (ref "C7") (pin "2") (pinfunction "2_2") (pintype "passive"))
      (node (ref "C8") (pin "2") (pinfunction "2_2") (pintype "passive"))
      (node (ref "C9") (pin "2") (pinfunction "2_2") (pintype "passive"))
      (node (ref "HI-LO-1") (pin "2") (pinfunction "GND_2") (pintype "power_in"))
      (node (ref "HI-LO-2") (pin "2") (pinfunction "GND_2") (pintype "power_in"))
      (node (ref "J1") (pin "1") (pinfunction "1_1") (pintype "passive"))
      (node (ref "J1") (pin "2") (pinfunction "2_2") (pintype "passive"))
      (node (ref "J2") (pin "3") (pinfunction "VSS(GND)_3") (pintype "power_in"))
      (node (ref "J2") (pin "5") (pinfunction "ICSP_CLK/PGC_5") (pintype "output"))
      (node (ref "J3") (pin "4") (pinfunction "4_4") (pintype "passive"))
      (node (ref "LO-HI-1") (pin "2") (pinfunction "GND_2") (pintype "power_in"))
      (node (ref "LO-HI-2") (pin "2") (pinfunction "GND_2") (pintype "power_in"))
      (node (ref "MIC") (pin "2") (pinfunction "GND_2") (pintype "bidirectional"))
      (node (ref "MSP1") (pin "26") (pinfunction "DVSS1_26") (pintype "bidirectional"))
      (node (ref "MSP1") (pin "57") (pinfunction "DVSS2_57") (pintype "bidirectional"))
      (node (ref "MSP1") (pin "80") (pinfunction "AVSS3_80") (pintype "bidirectional"))
      (node (ref "MSP1") (pin "83") (pinfunction "AVSS1_83") (pintype "bidirectional"))
      (node (ref "MSP1") (pin "86") (pinfunction "AVSS2_86") (pintype "bidirectional"))
      (node (ref "MSP1") (pin "98") (pinfunction "DVSS3_98") (pintype "bidirectional"))
      (node (ref "NCP") (pin "2") (pinfunction "GND_2") (pintype "bidirectional"))
      (node (ref "R1") (pin "2") (pinfunction "2_2") (pintype "passive"))
      (node (ref "R10") (pin "2") (pinfunction "2_2") (pintype "passive"))
      (node (ref "R12") (pin "2") (pinfunction "2_2") (pintype "passive"))
      (node (ref "R15") (pin "1") (pinfunction "1_1") (pintype "passive"))
      (node (ref "R18") (pin "1") (pinfunction "1_1") (pintype "passive"))
      (node (ref "R20") (pin "1") (pinfunction "1_1") (pintype "passive"))
      (node (ref "R25") (pin "2") (pinfunction "2_2") (pintype "passive"))
      (node (ref "R28") (pin "2") (pinfunction "2_2") (pintype "passive"))
      (node (ref "R33") (pin "2") (pinfunction "2_2") (pintype "passive"))
      (node (ref "R6") (pin "1") (pinfunction "1_1") (pintype "passive"))
      (node (ref "SOLAR1") (pin "1") (pinfunction "1_1") (pintype "passive"))
      (node (ref "SOLAR2") (pin "1") (pinfunction "1_1") (pintype "passive"))
      (node (ref "TM1") (pin "1") (pinfunction "A_1") (pintype "passive"))
      (node (ref "TM2") (pin "1") (pinfunction "A_1") (pintype "passive"))
      (node (ref "TM3") (pin "1") (pinfunction "A_1") (pintype "passive"))
      (node (ref "TM4") (pin "1") (pinfunction "A_1") (pintype "passive"))
      (node (ref "TM5") (pin "1") (pinfunction "A_1") (pintype "passive"))
      (node (ref "TM6") (pin "1") (pinfunction "A_1") (pintype "passive"))
      (node (ref "TM7") (pin "1") (pinfunction "A_1") (pintype "passive"))
      (node (ref "TM8") (pin "1") (pinfunction "A_1") (pintype "passive"))
      (node (ref "U10") (pin "4") (pinfunction "VCC-_4") (pintype "bidirectional"))
      (node (ref "U11") (pin "10") (pinfunction "LB_10") (pintype "bidirectional"))
      (node (ref "U11") (pin "13") (pinfunction "LA_13") (pintype "passive"))
      (node (ref "U11") (pin "4") (pinfunction "A0_4") (pintype "bidirectional"))
      (node (ref "U11") (pin "5") (pinfunction "A1_5") (pintype "bidirectional"))
      (node (ref "U11") (pin "6") (pinfunction "A2_6") (pintype "bidirectional"))
      (node (ref "U11") (pin "7") (pinfunction "GND_7") (pintype "bidirectional"))
      (node (ref "U11") (pin "TH") (pinfunction "GND_TH") (pintype "bidirectional"))
      (node (ref "U12") (pin "10") (pinfunction "LB_10") (pintype "bidirectional"))
      (node (ref "U12") (pin "13") (pinfunction "LA_13") (pintype "passive"))
      (node (ref "U12") (pin "4") (pinfunction "A0_4") (pintype "bidirectional"))
      (node (ref "U12") (pin "5") (pinfunction "A1_5") (pintype "bidirectional"))
      (node (ref "U12") (pin "6") (pinfunction "A2_6") (pintype "bidirectional"))
      (node (ref "U12") (pin "7") (pinfunction "GND_7") (pintype "bidirectional"))
      (node (ref "U12") (pin "TH") (pinfunction "GND_TH") (pintype "bidirectional"))
      (node (ref "U3") (pin "10") (pinfunction "EXTI_10") (pintype "bidirectional"))
      (node (ref "U3") (pin "2") (pinfunction "WDI_2") (pintype "bidirectional"))
      (node (ref "U3") (pin "9") (pinfunction "VSS_9") (pintype "bidirectional"))
      (node (ref "U3") (pin "TH") (pinfunction "VSS_TH") (pintype "bidirectional"))
      (node (ref "U4") (pin "3") (pinfunction "GND_3") (pintype "bidirectional"))
      (node (ref "U5") (pin "10") (pinfunction "LB_10") (pintype "bidirectional"))
      (node (ref "U5") (pin "13") (pinfunction "LA_13") (pintype "passive"))
      (node (ref "U5") (pin "4") (pinfunction "A0_4") (pintype "bidirectional"))
      (node (ref "U5") (pin "5") (pinfunction "A1_5") (pintype "bidirectional"))
      (node (ref "U5") (pin "6") (pinfunction "A2_6") (pintype "bidirectional"))
      (node (ref "U5") (pin "7") (pinfunction "GND_7") (pintype "bidirectional"))
      (node (ref "U5") (pin "TH") (pinfunction "GND_TH") (pintype "bidirectional"))
      (node (ref "U6") (pin "2") (pinfunction "GND_2") (pintype "bidirectional"))
      (node (ref "U7") (pin "4") (pinfunction "VCC-_4") (pintype "bidirectional"))
      (node (ref "U8") (pin "10") (pinfunction "LB_10") (pintype "bidirectional"))
      (node (ref "U8") (pin "13") (pinfunction "LA_13") (pintype "passive"))
      (node (ref "U8") (pin "4") (pinfunction "A0_4") (pintype "bidirectional"))
      (node (ref "U8") (pin "5") (pinfunction "A1_5") (pintype "bidirectional"))
      (node (ref "U8") (pin "6") (pinfunction "A2_6") (pintype "bidirectional"))
      (node (ref "U8") (pin "7") (pinfunction "GND_7") (pintype "bidirectional"))
      (node (ref "U8") (pin "TH") (pinfunction "GND_TH") (pintype "bidirectional"))
      (node (ref "U9") (pin "2") (pinfunction "GND_2") (pintype "bidirectional"))
      (node (ref "ZENER") (pin "ANODE") (pinfunction "A_ANODE") (pintype "passive"))
      (node (ref "ZENER1") (pin "ANODE") (pinfunction "A_ANODE") (pintype "passive"))
      (node (ref "ZENER2") (pin "ANODE") (pinfunction "A_ANODE") (pintype "passive"))
    )
    (net (code "22") (name "HARVESTER_IN") (class "Default")
      (node (ref "D1") (pin "C") (pinfunction "C_C") (pintype "passive"))
      (node (ref "D2") (pin "C") (pinfunction "C_C") (pintype "passive"))
      (node (ref "JP14") (pin "1") (pinfunction "1_1") (pintype "passive"))
      (node (ref "S1") (pin "1") (pinfunction "O_1") (pintype "passive"))
    )
    (net (code "23") (name "HI-LO-DIFF-1") (class "Default")
      (node (ref "HI-LO-2") (pin "4") (pinfunction "OUT_4") (pintype "output"))
      (node (ref "JP8") (pin "1") (pinfunction "1_1") (pintype "passive"))
      (node (ref "MSP1") (pin "51") (pinfunction "P2.0/UCA0SIMO/UCA0TXD/TB0.6/TB0CLK_51") (pintype "bidirectional"))
      (node (ref "R30") (pin "2") (pinfunction "2_2") (pintype "passive"))
    )
    (net (code "24") (name "HI-LO-DIFF-2") (class "Default")
      (node (ref "HI-LO-1") (pin "4") (pinfunction "OUT_4") (pintype "output"))
      (node (ref "JP29") (pin "1") (pinfunction "1_1") (pintype "passive"))
      (node (ref "MSP1") (pin "49") (pinfunction "P2.2/UCA0CLK/TB0.4/RTCCLK_49") (pintype "bidirectional"))
      (node (ref "R4") (pin "1") (pinfunction "1_1") (pintype "passive"))
    )
    (net (code "25") (name "LED_1") (class "Default")
      (node (ref "LED1") (pin "A") (pinfunction "A_A") (pintype "passive"))
      (node (ref "MSP1") (pin "13") (pinfunction "P6.6/TB0.2/COM3_13") (pintype "bidirectional"))
    )
    (net (code "26") (name "LED_2") (class "Default")
      (node (ref "LED2") (pin "A") (pinfunction "A_A") (pintype "passive"))
      (node (ref "MSP1") (pin "12") (pinfunction "P6.5/TB0.1/COM2_12") (pintype "bidirectional"))
    )
    (net (code "27") (name "LO-HI-DIFF-1") (class "Default")
      (node (ref "JP9") (pin "1") (pinfunction "1_1") (pintype "passive"))
      (node (ref "LO-HI-2") (pin "4") (pinfunction "OUT_4") (pintype "output"))
      (node (ref "MSP1") (pin "50") (pinfunction "P2.1/UCA0SOMI/UCA0RXD/TB0.5/DMAE0_50") (pintype "bidirectional"))
      (node (ref "R34") (pin "1") (pinfunction "1_1") (pintype "passive"))
    )
    (net (code "28") (name "LO-HI-DIFF-2") (class "Default")
      (node (ref "JP30") (pin "1") (pinfunction "1_1") (pintype "passive"))
      (node (ref "LO-HI-1") (pin "4") (pinfunction "OUT_4") (pintype "output"))
      (node (ref "MSP1") (pin "48") (pinfunction "P2.3/UCA0STE/TB0OUTH_48") (pintype "bidirectional"))
      (node (ref "R26") (pin "1") (pinfunction "1_1") (pintype "passive"))
    )
    (net (code "29") (name "MISO") (class "Default")
      (node (ref "J4") (pin "2") (pinfunction "2_2") (pintype "passive"))
      (node (ref "MSP1") (pin "5") (pinfunction "P1.7/UCB0SOMI/UCB0SCL/TA0.2_5") (pintype "bidirectional"))
    )
    (net (code "30") (name "MOSI") (class "Default")
      (node (ref "J4") (pin "4") (pinfunction "4_4") (pintype "passive"))
      (node (ref "MSP1") (pin "4") (pinfunction "P1.6/UCB0SIMO/UCB0SDA/TA0.1_4") (pintype "bidirectional"))
    )
    (net (code "31") (name "Net-(LED1-PadC)") (class "Default")
      (node (ref "LED1") (pin "C") (pinfunction "C_C") (pintype "passive"))
      (node (ref "R12") (pin "1") (pinfunction "1_1") (pintype "passive"))
    )
    (net (code "32") (name "Net-(LED2-PadC)") (class "Default")
      (node (ref "LED2") (pin "C") (pinfunction "C_C") (pintype "passive"))
      (node (ref "R25") (pin "1") (pinfunction "1_1") (pintype "passive"))
    )
    (net (code "33") (name "Net-(MIC-HTH)") (class "Default")
      (node (ref "MIC") (pin "1") (pinfunction "HTH_1") (pintype "bidirectional"))
      (node (ref "R14") (pin "1") (pinfunction "1_1") (pintype "passive"))
      (node (ref "R15") (pin "2") (pinfunction "2_2") (pintype "passive"))
    )
    (net (code "34") (name "Net-(MIC-LTH)") (class "Default")
      (node (ref "MIC") (pin "3") (pinfunction "LTH_3") (pintype "bidirectional"))
      (node (ref "R13") (pin "1") (pinfunction "1_1") (pintype "passive"))
      (node (ref "R14") (pin "2") (pinfunction "2_2") (pintype "passive"))
    )
    (net (code "35") (name "Net-(MSP1-P3.6{slash}UCA1CLK{slash}TB0.2{slash}S23)") (class "Default")
      (node (ref "JP49") (pin "1") (pinfunction "1_1") (pintype "passive"))
      (node (ref "MSP1") (pin "42") (pinfunction "P3.6/UCA1CLK/TB0.2/S23_42") (pintype "bidirectional"))
    )
    (net (code "36") (name "Net-(MSP1-P3.7{slash}UCA1STE{slash}TB0.3{slash}S22)") (class "Default")
      (node (ref "JP48") (pin "1") (pinfunction "1_1") (pintype "passive"))
      (node (ref "MSP1") (pin "43") (pinfunction "P3.7/UCA1STE/TB0.3/S22_43") (pintype "bidirectional"))
    )
    (net (code "37") (name "Net-(MSP1-P4.2{slash}UCA0SIMO{slash}UCA0TXD{slash}UCB1CLK)") (class "Default")
      (node (ref "JP47") (pin "1") (pinfunction "1_1") (pintype "passive"))
      (node (ref "MSP1") (pin "100") (pinfunction "P4.2/UCA0SIMO/UCA0TXD/UCB1CLK_100") (pintype "bidirectional"))
    )
    (net (code "38") (name "Net-(MSP1-P4.3{slash}UCA0SOMI{slash}UCA0RXD{slash}UCB1STE)") (class "Default")
      (node (ref "JP46") (pin "1") (pinfunction "1_1") (pintype "passive"))
      (node (ref "MSP1") (pin "1") (pinfunction "P4.3/UCA0SOMI/UCA0RXD/UCB1STE_1") (pintype "bidirectional"))
    )
    (net (code "39") (name "Net-(MSP1-P8.0{slash}RTCCLK{slash}S21)") (class "Default")
      (node (ref "JP44") (pin "1") (pinfunction "1_1") (pintype "passive"))
      (node (ref "MSP1") (pin "44") (pinfunction "P8.0/RTCCLK/S21_44") (pintype "bidirectional"))
    )
    (net (code "40") (name "Net-(MSP1-P8.1{slash}DMAE0{slash}S20)") (class "Default")
      (node (ref "JP45") (pin "1") (pinfunction "1_1") (pintype "passive"))
      (node (ref "MSP1") (pin "45") (pinfunction "P8.1/DMAE0/S20_45") (pintype "bidirectional"))
    )
    (net (code "41") (name "Net-(R10-Pad1)") (class "Default")
      (node (ref "R10") (pin "1") (pinfunction "1_1") (pintype "passive"))
      (node (ref "R2") (pin "2") (pinfunction "2_2") (pintype "passive"))
      (node (ref "R9") (pin "2") (pinfunction "2_2") (pintype "passive"))
    )
    (net (code "42") (name "Net-(R27-Pad2)") (class "Default")
      (node (ref "R27") (pin "2") (pinfunction "2_2") (pintype "passive"))
      (node (ref "R32") (pin "2") (pinfunction "2_2") (pintype "passive"))
      (node (ref "R33") (pin "1") (pinfunction "1_1") (pintype "passive"))
    )
    (net (code "43") (name "Net-(U3-VBAT)") (class "Default")
      (node (ref "C10") (pin "2") (pinfunction "2_2") (pintype "passive"))
      (node (ref "U3") (pin "5") (pinfunction "VBAT_5") (pintype "bidirectional"))
    )
    (net (code "44") (name "Net-(U4-VOUT)") (class "Default")
      (node (ref "R19") (pin "2") (pinfunction "2_2") (pintype "passive"))
      (node (ref "U4") (pin "2") (pinfunction "VOUT_2") (pintype "bidirectional"))
    )
    (net (code "45") (name "Net-(U6-VBIAS)") (class "Default")
      (node (ref "C12") (pin "1") (pinfunction "1_1") (pintype "passive"))
      (node (ref "D4") (pin "C") (pinfunction "C_C") (pintype "passive"))
      (node (ref "R21") (pin "2") (pinfunction "2_2") (pintype "passive"))
      (node (ref "U6") (pin "4") (pinfunction "VIN_4") (pintype "bidirectional"))
      (node (ref "U6") (pin "5") (pinfunction "VBIAS_5") (pintype "bidirectional"))
    )
    (net (code "46") (name "Net-(U7A-OUT1)") (class "Default")
      (node (ref "D4") (pin "A") (pinfunction "A_A") (pintype "passive"))
      (node (ref "U7") (pin "1") (pinfunction "OUT1_1") (pintype "output"))
    )
    (net (code "47") (name "Net-(U9-VBIAS)") (class "Default")
      (node (ref "C13") (pin "1") (pinfunction "1_1") (pintype "passive"))
      (node (ref "D5") (pin "C") (pinfunction "C_C") (pintype "passive"))
      (node (ref "R23") (pin "2") (pinfunction "2_2") (pintype "passive"))
      (node (ref "U9") (pin "4") (pinfunction "VIN_4") (pintype "bidirectional"))
      (node (ref "U9") (pin "5") (pinfunction "VBIAS_5") (pintype "bidirectional"))
    )
    (net (code "48") (name "Net-(U10A-OUT1)") (class "Default")
      (node (ref "D5") (pin "A") (pinfunction "A_A") (pintype "passive"))
      (node (ref "U10") (pin "1") (pinfunction "OUT1_1") (pintype "output"))
    )
    (net (code "49") (name "POWER_IN") (class "Default")
      (node (ref "C4") (pin "2") (pinfunction "2_2") (pintype "passive"))
      (node (ref "JP11") (pin "1") (pinfunction "1_1") (pintype "passive"))
      (node (ref "MIC") (pin "5") (pinfunction "VDD_5") (pintype "bidirectional"))
      (node (ref "R13") (pin "2") (pinfunction "2_2") (pintype "passive"))
      (node (ref "S1") (pin "2") (pinfunction "P_2") (pintype "passive"))
      (node (ref "ZENER2") (pin "CATHODE") (pinfunction "C_CATHODE") (pintype "passive"))
    )
    (net (code "50") (name "RADIO_GATE") (class "Default")
      (node (ref "JP39") (pin "2") (pinfunction "2_2") (pintype "passive"))
      (node (ref "U9") (pin "6") (pinfunction "ON_6") (pintype "bidirectional"))
    )
    (net (code "51") (name "RADIO_POT_1") (class "Default")
      (node (ref "JP2") (pin "1") (pinfunction "1_1") (pintype "passive"))
      (node (ref "R24") (pin "2") (pinfunction "2_2") (pintype "passive"))
      (node (ref "TM1") (pin "2") (pinfunction "S_2") (pintype "passive"))
      (node (ref "U10") (pin "3") (pinfunction "IN1+_3") (pintype "input"))
      (node (ref "U8") (pin "14") (pinfunction "WA_14") (pintype "passive"))
    )
    (net (code "52") (name "RADIO_POT_2") (class "Default")
      (node (ref "JP15") (pin "1") (pinfunction "1_1") (pintype "passive"))
      (node (ref "R23") (pin "1") (pinfunction "1_1") (pintype "passive"))
      (node (ref "TM2") (pin "2") (pinfunction "S_2") (pintype "passive"))
      (node (ref "U10") (pin "5") (pinfunction "IN1+_5") (pintype "input"))
      (node (ref "U8") (pin "11") (pinfunction "WB_11") (pintype "bidirectional"))
    )
    (net (code "53") (name "RADIO_UFOP_GATE") (class "Default")
      (node (ref "JP17") (pin "1") (pinfunction "1_1") (pintype "passive"))
      (node (ref "JP39") (pin "1") (pinfunction "1_1") (pintype "passive"))
      (node (ref "MSP1") (pin "9") (pinfunction "P6.2/COUT/R03_9") (pintype "bidirectional"))
    )
    (net (code "54") (name "RADIO_UFOP_INT") (class "Default")
      (node (ref "JP16") (pin "1") (pinfunction "1_1") (pintype "passive"))
      (node (ref "MSP1") (pin "10") (pinfunction "P6.3/COM0_10") (pintype "bidirectional"))
      (node (ref "U10") (pin "7") (pinfunction "OUT1_7") (pintype "output"))
      (node (ref "ZENER") (pin "CATHODE") (pinfunction "C_CATHODE") (pintype "passive"))
    )
    (net (code "55") (name "RADIO_UFOP_PWR") (class "Default")
      (node (ref "JP38") (pin "2") (pinfunction "2_2") (pintype "passive"))
      (node (ref "R24") (pin "1") (pinfunction "1_1") (pintype "passive"))
      (node (ref "U10") (pin "8") (pinfunction "VCC+_8") (pintype "bidirectional"))
      (node (ref "U8") (pin "1") (pinfunction "VDD_1") (pintype "bidirectional"))
    )
    (net (code "56") (name "RADIO_UFOP_VCC") (class "Default")
      (node (ref "J3") (pin "3") (pinfunction "3_3") (pintype "passive"))
      (node (ref "U9") (pin "1") (pinfunction "VOUT_1") (pintype "bidirectional"))
    )
    (net (code "57") (name "REF") (class "Default")
      (node (ref "JP32") (pin "1") (pinfunction "1_1") (pintype "passive"))
      (node (ref "R19") (pin "1") (pinfunction "1_1") (pintype "passive"))
      (node (ref "R20") (pin "2") (pinfunction "2_2") (pintype "passive"))
      (node (ref "U10") (pin "2") (pinfunction "IN1-_2") (pintype "input"))
      (node (ref "U10") (pin "6") (pinfunction "IN1-_6") (pintype "input"))
      (node (ref "U7") (pin "2") (pinfunction "IN1-_2") (pintype "input"))
      (node (ref "U7") (pin "6") (pinfunction "IN1-_6") (pintype "input"))
    )
    (net (code "58") (name "REFPWR") (class "Default")
      (node (ref "JP41") (pin "2") (pinfunction "2_2") (pintype "passive"))
      (node (ref "U4") (pin "1") (pinfunction "VIN_1") (pintype "bidirectional"))
    )
    (net (code "59") (name "RST") (class "Default")
      (node (ref "C3") (pin "2") (pinfunction "2_2") (pintype "passive"))
      (node (ref "J2") (pin "1") (pinfunction "VPP/MCLR_1") (pintype "passive"))
      (node (ref "JP25") (pin "1") (pinfunction "1_1") (pintype "passive"))
      (node (ref "MSP1") (pin "29") (pinfunction "RST/NMI/SBWTDIO_29") (pintype "bidirectional"))
      (node (ref "R11") (pin "1") (pinfunction "1_1") (pintype "passive"))
    )
    (net (code "60") (name "SCLK") (class "Default")
      (node (ref "J4") (pin "3") (pinfunction "3_3") (pintype "passive"))
      (node (ref "MSP1") (pin "2") (pinfunction "P1.4/UCB0CLK/UCA0STE/TA1.0/S1_2") (pintype "bidirectional"))
    )
    (net (code "61") (name "SCL_CTRL") (class "Default")
      (node (ref "JP23") (pin "1") (pinfunction "1_1") (pintype "passive"))
      (node (ref "MSP1") (pin "25") (pinfunction "P3.2/UCB1SOMI/UCB1SCL/S32_25") (pintype "bidirectional"))
      (node (ref "R16") (pin "1") (pinfunction "1_1") (pintype "passive"))
      (node (ref "U11") (pin "2") (pinfunction "SCL_2") (pintype "bidirectional"))
      (node (ref "U12") (pin "2") (pinfunction "SCL_2") (pintype "bidirectional"))
      (node (ref "U3") (pin "7") (pinfunction "SCL_7") (pintype "bidirectional"))
      (node (ref "U5") (pin "2") (pinfunction "SCL_2") (pintype "bidirectional"))
      (node (ref "U8") (pin "2") (pinfunction "SCL_2") (pintype "bidirectional"))
    )
    (net (code "62") (name "SDA_CTRL") (class "Default")
      (node (ref "JP22") (pin "1") (pinfunction "1_1") (pintype "passive"))
      (node (ref "MSP1") (pin "24") (pinfunction "P3.1/UCB1SIMO/UCB1SDA/S33_24") (pintype "bidirectional"))
      (node (ref "R17") (pin "1") (pinfunction "1_1") (pintype "passive"))
      (node (ref "U11") (pin "3") (pinfunction "SDA_3") (pintype "bidirectional"))
      (node (ref "U12") (pin "3") (pinfunction "SDA_3") (pintype "bidirectional"))
      (node (ref "U3") (pin "6") (pinfunction "SDA_6") (pintype "bidirectional"))
      (node (ref "U5") (pin "3") (pinfunction "SDA_3") (pintype "bidirectional"))
      (node (ref "U8") (pin "3") (pinfunction "SDA_3") (pintype "bidirectional"))
    )
    (net (code "63") (name "SOLAR1") (class "Default")
      (node (ref "D1") (pin "A") (pinfunction "A_A") (pintype "passive"))
      (node (ref "JP34") (pin "2") (pinfunction "2_2") (pintype "passive"))
      (node (ref "JP36") (pin "2") (pinfunction "2_2") (pintype "passive"))
      (node (ref "R7") (pin "1") (pinfunction "1_1") (pintype "passive"))
      (node (ref "SOL1") (pin "1") (pinfunction "1_1") (pintype "passive"))
      (node (ref "SOLAR1") (pin "2") (pinfunction "2_2") (pintype "passive"))
    )
    (net (code "64") (name "SOLAR1-1") (class "Default")
      (node (ref "C16") (pin "1") (pinfunction "1_1") (pintype "passive"))
      (node (ref "JP34") (pin "1") (pinfunction "1_1") (pintype "passive"))
    )
    (net (code "65") (name "SOLAR1-2") (class "Default")
      (node (ref "C17") (pin "1") (pinfunction "1_1") (pintype "passive"))
      (node (ref "JP36") (pin "1") (pinfunction "1_1") (pintype "passive"))
    )
    (net (code "66") (name "SOLAR1IN") (class "Default")
      (node (ref "C15") (pin "2") (pinfunction "2_2") (pintype "passive"))
      (node (ref "JP26") (pin "1") (pinfunction "1_1") (pintype "passive"))
      (node (ref "JP3") (pin "1") (pinfunction "1_1") (pintype "passive"))
      (node (ref "R18") (pin "2") (pinfunction "2_2") (pintype "passive"))
      (node (ref "R7") (pin "2") (pinfunction "2_2") (pintype "passive"))
    )
    (net (code "67") (name "SOLAR1MC") (class "Default")
      (node (ref "JP3") (pin "2") (pinfunction "2_2") (pintype "passive"))
      (node (ref "MSP1") (pin "65") (pinfunction "P1.1/TA0.2/TA1CLK/COUT/A1/C1/VREF+/VEREF+_65") (pintype "bidirectional"))
    )
    (net (code "68") (name "SOLAR2") (class "Default")
      (node (ref "D2") (pin "A") (pinfunction "A_A") (pintype "passive"))
      (node (ref "JP4") (pin "2") (pinfunction "2_2") (pintype "passive"))
      (node (ref "JP5") (pin "2") (pinfunction "2_2") (pintype "passive"))
      (node (ref "JP6") (pin "1") (pinfunction "1_1") (pintype "passive"))
      (node (ref "R5") (pin "1") (pinfunction "1_1") (pintype "passive"))
      (node (ref "SOLAR2") (pin "2") (pinfunction "2_2") (pintype "passive"))
    )
    (net (code "69") (name "SOLAR2-1") (class "Default")
      (node (ref "C2") (pin "1") (pinfunction "1_1") (pintype "passive"))
      (node (ref "JP4") (pin "1") (pinfunction "1_1") (pintype "passive"))
    )
    (net (code "70") (name "SOLAR2-2") (class "Default")
      (node (ref "C1") (pin "1") (pinfunction "1_1") (pintype "passive"))
      (node (ref "JP5") (pin "1") (pinfunction "1_1") (pintype "passive"))
    )
    (net (code "71") (name "SOLAR2IN") (class "Default")
      (node (ref "C14") (pin "2") (pinfunction "2_2") (pintype "passive"))
      (node (ref "JP27") (pin "1") (pinfunction "1_1") (pintype "passive"))
      (node (ref "JP43") (pin "1") (pinfunction "1_1") (pintype "passive"))
      (node (ref "R5") (pin "2") (pinfunction "2_2") (pintype "passive"))
      (node (ref "R6") (pin "2") (pinfunction "2_2") (pintype "passive"))
    )
    (net (code "72") (name "SOLAR2MC") (class "Default")
      (node (ref "JP43") (pin "2") (pinfunction "2_2") (pintype "passive"))
      (node (ref "MSP1") (pin "66") (pinfunction "P1.0/TA0.1/DMAE0/RTCCLK/A0/C0/VREF-/VEREF-_66") (pintype "bidirectional"))
    )
    (net (code "73") (name "TEST") (class "Default")
      (node (ref "J2") (pin "6") (pinfunction "LVP_6") (pintype "bidirectional"))
      (node (ref "JP24") (pin "1") (pinfunction "1_1") (pintype "passive"))
      (node (ref "MSP1") (pin "28") (pinfunction "TEST/SBWTCK_28") (pintype "bidirectional"))
    )
    (net (code "74") (name "TLVPWR1") (class "Default")
      (node (ref "HI-LO-2") (pin "5") (pinfunction "V+_5") (pintype "power_in"))
      (node (ref "JP1") (pin "2") (pinfunction "2_2") (pintype "passive"))
      (node (ref "R8") (pin "1") (pinfunction "1_1") (pintype "passive"))
      (node (ref "R9") (pin "1") (pinfunction "1_1") (pintype "passive"))
    )
    (net (code "75") (name "TLVPWR2") (class "Default")
      (node (ref "JP33") (pin "2") (pinfunction "2_2") (pintype "passive"))
      (node (ref "LO-HI-2") (pin "5") (pinfunction "V+_5") (pintype "power_in"))
      (node (ref "R3") (pin "1") (pinfunction "1_1") (pintype "passive"))
    )
    (net (code "76") (name "TLVPWR3") (class "Default")
      (node (ref "HI-LO-1") (pin "5") (pinfunction "V+_5") (pintype "power_in"))
      (node (ref "JP35") (pin "2") (pinfunction "2_2") (pintype "passive"))
      (node (ref "R31") (pin "1") (pinfunction "1_1") (pintype "passive"))
      (node (ref "R32") (pin "1") (pinfunction "1_1") (pintype "passive"))
    )
    (net (code "77") (name "TLVPWR4") (class "Default")
      (node (ref "JP37") (pin "2") (pinfunction "2_2") (pintype "passive"))
      (node (ref "LO-HI-1") (pin "5") (pinfunction "V+_5") (pintype "power_in"))
      (node (ref "R29") (pin "1") (pinfunction "1_1") (pintype "passive"))
    )
    (net (code "78") (name "TRIG") (class "Default")
      (node (ref "J1") (pin "4") (pinfunction "4_4") (pintype "passive"))
      (node (ref "MSP1") (pin "22") (pinfunction "P5.3/UCB1STE/S35_22") (pintype "bidirectional"))
    )
    (net (code "79") (name "VCC") (class "Default")
      (node (ref "C5") (pin "1") (pinfunction "1_1") (pintype "passive"))
      (node (ref "C6") (pin "1") (pinfunction "1_1") (pintype "passive"))
      (node (ref "C7") (pin "1") (pinfunction "1_1") (pintype "passive"))
      (node (ref "C8") (pin "1") (pinfunction "1_1") (pintype "passive"))
      (node (ref "C9") (pin "1") (pinfunction "1_1") (pintype "passive"))
      (node (ref "J2") (pin "2") (pinfunction "VDD_2") (pintype "power_in"))
      (node (ref "JP1") (pin "1") (pinfunction "1_1") (pintype "passive"))
      (node (ref "JP13") (pin "1") (pinfunction "1_1") (pintype "passive"))
      (node (ref "JP33") (pin "1") (pinfunction "1_1") (pintype "passive"))
      (node (ref "JP35") (pin "1") (pinfunction "1_1") (pintype "passive"))
      (node (ref "JP37") (pin "1") (pinfunction "1_1") (pintype "passive"))
      (node (ref "MSP1") (pin "27") (pinfunction "DVCC1_27") (pintype "bidirectional"))
      (node (ref "MSP1") (pin "58") (pinfunction "DVCC2_58") (pintype "bidirectional"))
      (node (ref "MSP1") (pin "79") (pinfunction "AVCC1_79") (pintype "bidirectional"))
      (node (ref "MSP1") (pin "99") (pinfunction "DVCC3_99") (pintype "bidirectional"))
      (node (ref "NCP") (pin "3") (pinfunction "OUT_3") (pintype "bidirectional"))
      (node (ref "R11") (pin "2") (pinfunction "2_2") (pintype "passive"))
      (node (ref "R16") (pin "2") (pinfunction "2_2") (pintype "passive"))
      (node (ref "R17") (pin "2") (pinfunction "2_2") (pintype "passive"))
      (node (ref "U3") (pin "13") (pinfunction "VCC_13") (pintype "bidirectional"))
    )
    (net (code "80") (name "VIN") (class "Default")
      (node (ref "JP12") (pin "1") (pinfunction "1_1") (pintype "passive"))
      (node (ref "JP38") (pin "1") (pinfunction "1_1") (pintype "passive"))
      (node (ref "JP40") (pin "1") (pinfunction "1_1") (pintype "passive"))
      (node (ref "JP41") (pin "1") (pinfunction "1_1") (pintype "passive"))
      (node (ref "MIC") (pin "4") (pinfunction "OUT_4") (pintype "bidirectional"))
      (node (ref "NCP") (pin "1") (pinfunction "CE_1") (pintype "bidirectional"))
      (node (ref "NCP") (pin "4") (pinfunction "VIN_4") (pintype "bidirectional"))
      (node (ref "U11") (pin "1") (pinfunction "VDD_1") (pintype "bidirectional"))
      (node (ref "U12") (pin "1") (pinfunction "VDD_1") (pintype "bidirectional"))
    )
    (net (code "81") (name "WP_CTRL_DIFF_1") (class "Default")
      (node (ref "MSP1") (pin "60") (pinfunction "P8.5/A6/C6_60") (pintype "bidirectional"))
      (node (ref "U11") (pin "9") (pinfunction "WP_9") (pintype "bidirectional"))
    )
    (net (code "82") (name "WP_CTRL_DIFF_2") (class "Default")
      (node (ref "MSP1") (pin "61") (pinfunction "P8.6/A5/C5_61") (pintype "bidirectional"))
      (node (ref "U12") (pin "9") (pinfunction "WP_9") (pintype "bidirectional"))
    )
    (net (code "83") (name "WP_CTRL_ECHO") (class "Default")
      (node (ref "MSP1") (pin "14") (pinfunction "P2.4/TB0.3/COM4/S43_14") (pintype "bidirectional"))
      (node (ref "U5") (pin "9") (pinfunction "WP_9") (pintype "bidirectional"))
    )
    (net (code "84") (name "WP_CTRL_RADIO") (class "Default")
      (node (ref "MSP1") (pin "11") (pinfunction "P6.4/TB0.0/COM1_11") (pintype "bidirectional"))
      (node (ref "U8") (pin "9") (pinfunction "WP_9") (pintype "bidirectional"))
    )
    (net (code "85") (name "unconnected-(J2-ICSP_DAT{slash}PGD-Pad4)") (class "Default")
      (node (ref "J2") (pin "4") (pinfunction "ICSP_DAT/PGD_4") (pintype "bidirectional"))
    )
    (net (code "86") (name "unconnected-(JP1-Pad3)") (class "Default")
      (node (ref "JP1") (pin "3") (pinfunction "3_3") (pintype "passive"))
    )
    (net (code "87") (name "unconnected-(JP3-Pad3)") (class "Default")
      (node (ref "JP3") (pin "3") (pinfunction "3_3") (pintype "passive"))
    )
    (net (code "88") (name "unconnected-(JP4-Pad3)") (class "Default")
      (node (ref "JP4") (pin "3") (pinfunction "3_3") (pintype "passive"))
    )
    (net (code "89") (name "unconnected-(JP5-Pad3)") (class "Default")
      (node (ref "JP5") (pin "3") (pinfunction "3_3") (pintype "passive"))
    )
    (net (code "90") (name "unconnected-(JP33-Pad3)") (class "Default")
      (node (ref "JP33") (pin "3") (pinfunction "3_3") (pintype "passive"))
    )
    (net (code "91") (name "unconnected-(JP34-Pad3)") (class "Default")
      (node (ref "JP34") (pin "3") (pinfunction "3_3") (pintype "passive"))
    )
    (net (code "92") (name "unconnected-(JP35-Pad3)") (class "Default")
      (node (ref "JP35") (pin "3") (pinfunction "3_3") (pintype "passive"))
    )
    (net (code "93") (name "unconnected-(JP36-Pad3)") (class "Default")
      (node (ref "JP36") (pin "3") (pinfunction "3_3") (pintype "passive"))
    )
    (net (code "94") (name "unconnected-(JP37-Pad3)") (class "Default")
      (node (ref "JP37") (pin "3") (pinfunction "3_3") (pintype "passive"))
    )
    (net (code "95") (name "unconnected-(JP38-Pad3)") (class "Default")
      (node (ref "JP38") (pin "3") (pinfunction "3_3") (pintype "passive"))
    )
    (net (code "96") (name "unconnected-(JP39-Pad3)") (class "Default")
      (node (ref "JP39") (pin "3") (pinfunction "3_3") (pintype "passive"))
    )
    (net (code "97") (name "unconnected-(JP40-Pad3)") (class "Default")
      (node (ref "JP40") (pin "3") (pinfunction "3_3") (pintype "passive"))
    )
    (net (code "98") (name "unconnected-(JP41-Pad3)") (class "Default")
      (node (ref "JP41") (pin "3") (pinfunction "3_3") (pintype "passive"))
    )
    (net (code "99") (name "unconnected-(JP42-Pad3)") (class "Default")
      (node (ref "JP42") (pin "3") (pinfunction "3_3") (pintype "passive"))
    )
    (net (code "100") (name "unconnected-(JP43-Pad3)") (class "Default")
      (node (ref "JP43") (pin "3") (pinfunction "3_3") (pintype "passive"))
    )
    (net (code "101") (name "unconnected-(MSP1-ESICI-Pad77)") (class "Default")
      (node (ref "MSP1") (pin "77") (pinfunction "ESICI_77") (pintype "bidirectional"))
    )
    (net (code "102") (name "unconnected-(MSP1-ESICOM-Pad78)") (class "Default")
      (node (ref "MSP1") (pin "78") (pinfunction "ESICOM_78") (pintype "bidirectional"))
    )
    (net (code "103") (name "unconnected-(MSP1-ESIVCC-Pad75)") (class "Default")
      (node (ref "MSP1") (pin "75") (pinfunction "ESIVCC_75") (pintype "bidirectional"))
    )
    (net (code "104") (name "unconnected-(MSP1-ESIVSS-Pad76)") (class "Default")
      (node (ref "MSP1") (pin "76") (pinfunction "ESIVSS_76") (pintype "bidirectional"))
    )
    (net (code "105") (name "unconnected-(MSP1-P1.2{slash}TA1.1{slash}TA0CLK{slash}COUT{slash}A2{slash}C2-Pad64)") (class "Default")
      (node (ref "MSP1") (pin "64") (pinfunction "P1.2/TA1.1/TA0CLK/COUT/A2/C2_64") (pintype "bidirectional"))
    )
    (net (code "106") (name "unconnected-(MSP1-P1.3{slash}TA1.2{slash}ESITEST4{slash}A3{slash}C3-Pad63)") (class "Default")
      (node (ref "MSP1") (pin "63") (pinfunction "P1.3/TA1.2/ESITEST4/A3/C3_63") (pintype "bidirectional"))
    )
    (net (code "107") (name "unconnected-(MSP1-P2.5{slash}TB0.4{slash}COM5{slash}S42-Pad15)") (class "Default")
      (node (ref "MSP1") (pin "15") (pinfunction "P2.5/TB0.4/COM5/S42_15") (pintype "bidirectional"))
    )
    (net (code "108") (name "unconnected-(MSP1-P2.6{slash}TB0.5{slash}ESIC1OUT{slash}COM6{slash}S41-Pad16)") (class "Default")
      (node (ref "MSP1") (pin "16") (pinfunction "P2.6/TB0.5/ESIC1OUT/COM6/S41_16") (pintype "bidirectional"))
    )
    (net (code "109") (name "unconnected-(MSP1-P2.7{slash}TB0.6{slash}ESIC2OUT{slash}COM7{slash}S40-Pad17)") (class "Default")
      (node (ref "MSP1") (pin "17") (pinfunction "P2.7/TB0.6/ESIC2OUT/COM7/S40_17") (pintype "bidirectional"))
    )
    (net (code "110") (name "unconnected-(MSP1-P3.0{slash}UCB1CLK{slash}S34-Pad23)") (class "Default")
      (node (ref "MSP1") (pin "23") (pinfunction "P3.0/UCB1CLK/S34_23") (pintype "bidirectional"))
    )
    (net (code "111") (name "unconnected-(MSP1-P3.3{slash}TA1.1{slash}TB0CLK{slash}S26-Pad39)") (class "Default")
      (node (ref "MSP1") (pin "39") (pinfunction "P3.3/TA1.1/TB0CLK/S26_39") (pintype "bidirectional"))
    )
    (net (code "112") (name "unconnected-(MSP1-P3.4{slash}UCA1SIMO{slash}UCA1TXD{slash}TB0.0{slash}S25-Pad40)") (class "Default")
      (node (ref "MSP1") (pin "40") (pinfunction "P3.4/UCA1SIMO/UCA1TXD/TB0.0/S25_40") (pintype "bidirectional"))
    )
    (net (code "113") (name "unconnected-(MSP1-P3.5{slash}UCA1SOMI{slash}UCA1RXD{slash}TB0.1{slash}S24-Pad41)") (class "Default")
      (node (ref "MSP1") (pin "41") (pinfunction "P3.5/UCA1SOMI/UCA1RXD/TB0.1/S24_41") (pintype "bidirectional"))
    )
    (net (code "114") (name "unconnected-(MSP1-P4.0{slash}UCB1SIMO{slash}UCB1SDA{slash}MCLK{slash}S3-Pad96)") (class "Default")
      (node (ref "MSP1") (pin "96") (pinfunction "P4.0/UCB1SIMO/UCB1SDA/MCLK/S3_96") (pintype "bidirectional"))
    )
    (net (code "115") (name "unconnected-(MSP1-P4.1{slash}UCB1SOMI{slash}UCB1SCL{slash}ACLK{slash}S2-Pad97)") (class "Default")
      (node (ref "MSP1") (pin "97") (pinfunction "P4.1/UCB1SOMI/UCB1SCL/ACLK/S2_97") (pintype "bidirectional"))
    )
    (net (code "116") (name "unconnected-(MSP1-P4.4{slash}UCB1STE{slash}TA1CLK{slash}S8-Pad91)") (class "Default")
      (node (ref "MSP1") (pin "91") (pinfunction "P4.4/UCB1STE/TA1CLK/S8_91") (pintype "bidirectional"))
    )
    (net (code "117") (name "unconnected-(MSP1-P4.5{slash}UCB1CLK{slash}TA1.0{slash}S7-Pad92)") (class "Default")
      (node (ref "MSP1") (pin "92") (pinfunction "P4.5/UCB1CLK/TA1.0/S7_92") (pintype "bidirectional"))
    )
    (net (code "118") (name "unconnected-(MSP1-P4.6{slash}UCB1SIMO{slash}UCB1SDA{slash}TA1.1{slash}S6-Pad93)") (class "Default")
      (node (ref "MSP1") (pin "93") (pinfunction "P4.6/UCB1SIMO/UCB1SDA/TA1.1/S6_93") (pintype "bidirectional"))
    )
    (net (code "119") (name "unconnected-(MSP1-P4.7{slash}UCB1SOMI{slash}UCB1SCL{slash}TA1.2{slash}S5-Pad94)") (class "Default")
      (node (ref "MSP1") (pin "94") (pinfunction "P4.7/UCB1SOMI/UCB1SCL/TA1.2/S5_94") (pintype "bidirectional"))
    )
    (net (code "120") (name "unconnected-(MSP1-P5.1{slash}TA1.2{slash}S37-Pad20)") (class "Default")
      (node (ref "MSP1") (pin "20") (pinfunction "P5.1/TA1.2/S37_20") (pintype "bidirectional"))
    )
    (net (code "121") (name "unconnected-(MSP1-P5.4{slash}UCA1SIMO{slash}UCA1TXD{slash}S12-Pad87)") (class "Default")
      (node (ref "MSP1") (pin "87") (pinfunction "P5.4/UCA1SIMO/UCA1TXD/S12_87") (pintype "bidirectional"))
    )
    (net (code "122") (name "unconnected-(MSP1-P5.5{slash}UCA1SOMI{slash}UCA1RXD{slash}S11-Pad88)") (class "Default")
      (node (ref "MSP1") (pin "88") (pinfunction "P5.5/UCA1SOMI/UCA1RXD/S11_88") (pintype "bidirectional"))
    )
    (net (code "123") (name "unconnected-(MSP1-P5.6{slash}UCA1CLK{slash}S10-Pad89)") (class "Default")
      (node (ref "MSP1") (pin "89") (pinfunction "P5.6/UCA1CLK/S10_89") (pintype "bidirectional"))
    )
    (net (code "124") (name "unconnected-(MSP1-P5.7{slash}UCA1STE{slash}TB0CLK{slash}S9-Pad90)") (class "Default")
      (node (ref "MSP1") (pin "90") (pinfunction "P5.7/UCA1STE/TB0CLK/S9_90") (pintype "bidirectional"))
    )
    (net (code "125") (name "unconnected-(MSP1-P6.7{slash}TA0CLK{slash}S31-Pad34)") (class "Default")
      (node (ref "MSP1") (pin "34") (pinfunction "P6.7/TA0CLK/S31_34") (pintype "bidirectional"))
    )
    (net (code "126") (name "unconnected-(MSP1-P7.0{slash}TA0CLK{slash}S17-Pad52)") (class "Default")
      (node (ref "MSP1") (pin "52") (pinfunction "P7.0/TA0CLK/S17_52") (pintype "bidirectional"))
    )
    (net (code "127") (name "unconnected-(MSP1-P7.1{slash}TA0.0{slash}S16-Pad53)") (class "Default")
      (node (ref "MSP1") (pin "53") (pinfunction "P7.1/TA0.0/S16_53") (pintype "bidirectional"))
    )
    (net (code "128") (name "unconnected-(MSP1-P7.2{slash}TA0.1{slash}S15-Pad54)") (class "Default")
      (node (ref "MSP1") (pin "54") (pinfunction "P7.2/TA0.1/S15_54") (pintype "bidirectional"))
    )
    (net (code "129") (name "unconnected-(MSP1-P7.3{slash}TA0.2{slash}S14-Pad55)") (class "Default")
      (node (ref "MSP1") (pin "55") (pinfunction "P7.3/TA0.2/S14_55") (pintype "bidirectional"))
    )
    (net (code "130") (name "unconnected-(MSP1-P7.4{slash}SMCLK{slash}S13-Pad56)") (class "Default")
      (node (ref "MSP1") (pin "56") (pinfunction "P7.4/SMCLK/S13_56") (pintype "bidirectional"))
    )
    (net (code "131") (name "unconnected-(MSP1-P7.5{slash}TA0.2{slash}S30-Pad35)") (class "Default")
      (node (ref "MSP1") (pin "35") (pinfunction "P7.5/TA0.2/S30_35") (pintype "bidirectional"))
    )
    (net (code "132") (name "unconnected-(MSP1-P7.6{slash}TA0.1{slash}S29-Pad36)") (class "Default")
      (node (ref "MSP1") (pin "36") (pinfunction "P7.6/TA0.1/S29_36") (pintype "bidirectional"))
    )
    (net (code "133") (name "unconnected-(MSP1-P7.7{slash}TA1.2{slash}TB0OUTH{slash}S27-Pad38)") (class "Default")
      (node (ref "MSP1") (pin "38") (pinfunction "P7.7/TA1.2/TB0OUTH/S27_38") (pintype "bidirectional"))
    )
    (net (code "134") (name "unconnected-(MSP1-P8.2{slash}S19-Pad46)") (class "Default")
      (node (ref "MSP1") (pin "46") (pinfunction "P8.2/S19_46") (pintype "bidirectional"))
    )
    (net (code "135") (name "unconnected-(MSP1-P8.3{slash}MCLK{slash}S18-Pad47)") (class "Default")
      (node (ref "MSP1") (pin "47") (pinfunction "P8.3/MCLK/S18_47") (pintype "bidirectional"))
    )
    (net (code "136") (name "unconnected-(MSP1-P8.4{slash}A7{slash}C7-Pad59)") (class "Default")
      (node (ref "MSP1") (pin "59") (pinfunction "P8.4/A7/C7_59") (pintype "bidirectional"))
    )
    (net (code "137") (name "unconnected-(MSP1-P8.7{slash}A4{slash}C4-Pad62)") (class "Default")
      (node (ref "MSP1") (pin "62") (pinfunction "P8.7/A4/C4_62") (pintype "bidirectional"))
    )
    (net (code "138") (name "unconnected-(MSP1-P9.0{slash}ESICH0{slash}ESITEST0{slash}A8{slash}C8-Pad67)") (class "Default")
      (node (ref "MSP1") (pin "67") (pinfunction "P9.0/ESICH0/ESITEST0/A8/C8_67") (pintype "bidirectional"))
    )
    (net (code "139") (name "unconnected-(MSP1-P9.1{slash}ESICH1{slash}ESITEST1{slash}A9{slash}C9-Pad68)") (class "Default")
      (node (ref "MSP1") (pin "68") (pinfunction "P9.1/ESICH1/ESITEST1/A9/C9_68") (pintype "bidirectional"))
    )
    (net (code "140") (name "unconnected-(MSP1-P9.2{slash}ESICH2{slash}ESITEST2{slash}A10{slash}C10-Pad69)") (class "Default")
      (node (ref "MSP1") (pin "69") (pinfunction "P9.2/ESICH2/ESITEST2/A10/C10_69") (pintype "bidirectional"))
    )
    (net (code "141") (name "unconnected-(MSP1-P9.3{slash}ESICH3{slash}ESITEST3{slash}A11{slash}C11-Pad70)") (class "Default")
      (node (ref "MSP1") (pin "70") (pinfunction "P9.3/ESICH3/ESITEST3/A11/C11_70") (pintype "bidirectional"))
    )
    (net (code "142") (name "unconnected-(MSP1-P9.4{slash}ESICI0{slash}A12{slash}C12-Pad71)") (class "Default")
      (node (ref "MSP1") (pin "71") (pinfunction "P9.4/ESICI0/A12/C12_71") (pintype "bidirectional"))
    )
    (net (code "143") (name "unconnected-(MSP1-P9.5{slash}ESICI1{slash}A13{slash}C13-Pad72)") (class "Default")
      (node (ref "MSP1") (pin "72") (pinfunction "P9.5/ESICI1/A13/C13_72") (pintype "bidirectional"))
    )
    (net (code "144") (name "unconnected-(MSP1-P9.6{slash}ESICI2{slash}A14{slash}C14-Pad73)") (class "Default")
      (node (ref "MSP1") (pin "73") (pinfunction "P9.6/ESICI2/A14/C14_73") (pintype "bidirectional"))
    )
    (net (code "145") (name "unconnected-(MSP1-P9.7{slash}ESICI3{slash}A15{slash}C15-Pad74)") (class "Default")
      (node (ref "MSP1") (pin "74") (pinfunction "P9.7/ESICI3/A15/C15_74") (pintype "bidirectional"))
    )
    (net (code "146") (name "unconnected-(MSP1-P10.0{slash}SMCLK{slash}S4-Pad95)") (class "Default")
      (node (ref "MSP1") (pin "95") (pinfunction "P10.0/SMCLK/S4_95") (pintype "bidirectional"))
    )
    (net (code "147") (name "unconnected-(MSP1-P10.1{slash}TA0.0{slash}S28-Pad37)") (class "Default")
      (node (ref "MSP1") (pin "37") (pinfunction "P10.1/TA0.0/S28_37") (pintype "bidirectional"))
    )
    (net (code "148") (name "unconnected-(MSP1-PJ.0{slash}TDO{slash}TB0OUTH{slash}SMCLK{slash}SRSCG1-Pad30)") (class "Default")
      (node (ref "MSP1") (pin "30") (pinfunction "PJ.0/TDO/TB0OUTH/SMCLK/SRSCG1_30") (pintype "bidirectional"))
    )
    (net (code "149") (name "unconnected-(MSP1-PJ.1{slash}TDI{slash}TCLK{slash}MCLK{slash}SRSCG-Pad31)") (class "Default")
      (node (ref "MSP1") (pin "31") (pinfunction "PJ.1/TDI/TCLK/MCLK/SRSCG_31") (pintype "bidirectional"))
    )
    (net (code "150") (name "unconnected-(MSP1-PJ.2{slash}TMS{slash}ACLK{slash}SROSCOFF-Pad32)") (class "Default")
      (node (ref "MSP1") (pin "32") (pinfunction "PJ.2/TMS/ACLK/SROSCOFF_32") (pintype "bidirectional"))
    )
    (net (code "151") (name "unconnected-(MSP1-PJ.3{slash}TCK{slash}COUT{slash}SRCPUOFF-Pad33)") (class "Default")
      (node (ref "MSP1") (pin "33") (pinfunction "PJ.3/TCK/COUT/SRCPUOFF_33") (pintype "bidirectional"))
    )
    (net (code "152") (name "unconnected-(MSP1-PJ.4{slash}LFXIN-Pad84)") (class "Default")
      (node (ref "MSP1") (pin "84") (pinfunction "PJ.4/LFXIN_84") (pintype "bidirectional"))
    )
    (net (code "153") (name "unconnected-(MSP1-PJ.5{slash}LFXOUT-Pad85)") (class "Default")
      (node (ref "MSP1") (pin "85") (pinfunction "PJ.5/LFXOUT_85") (pintype "bidirectional"))
    )
    (net (code "154") (name "unconnected-(MSP1-PJ.6{slash}HFXIN-Pad82)") (class "Default")
      (node (ref "MSP1") (pin "82") (pinfunction "PJ.6/HFXIN_82") (pintype "bidirectional"))
    )
    (net (code "155") (name "unconnected-(MSP1-PJ.7{slash}HFXOUT-Pad81)") (class "Default")
      (node (ref "MSP1") (pin "81") (pinfunction "PJ.7/HFXOUT_81") (pintype "bidirectional"))
    )
    (net (code "156") (name "unconnected-(MSP1-R33{slash}LCDCAP-Pad6)") (class "Default")
      (node (ref "MSP1") (pin "6") (pinfunction "R33/LCDCAP_6") (pintype "bidirectional"))
    )
    (net (code "157") (name "unconnected-(TM1-E-Pad3)") (class "Default")
      (node (ref "TM1") (pin "3") (pinfunction "E_3") (pintype "passive"))
    )
    (net (code "158") (name "unconnected-(TM2-E-Pad3)") (class "Default")
      (node (ref "TM2") (pin "3") (pinfunction "E_3") (pintype "passive"))
    )
    (net (code "159") (name "unconnected-(TM3-E-Pad3)") (class "Default")
      (node (ref "TM3") (pin "3") (pinfunction "E_3") (pintype "passive"))
    )
    (net (code "160") (name "unconnected-(TM4-E-Pad3)") (class "Default")
      (node (ref "TM4") (pin "3") (pinfunction "E_3") (pintype "passive"))
    )
    (net (code "161") (name "unconnected-(TM5-E-Pad3)") (class "Default")
      (node (ref "TM5") (pin "3") (pinfunction "E_3") (pintype "passive"))
    )
    (net (code "162") (name "unconnected-(TM6-E-Pad3)") (class "Default")
      (node (ref "TM6") (pin "3") (pinfunction "E_3") (pintype "passive"))
    )
    (net (code "163") (name "unconnected-(TM7-E-Pad3)") (class "Default")
      (node (ref "TM7") (pin "3") (pinfunction "E_3") (pintype "passive"))
    )
    (net (code "164") (name "unconnected-(TM8-E-Pad3)") (class "Default")
      (node (ref "TM8") (pin "3") (pinfunction "E_3") (pintype "passive"))
    )
    (net (code "165") (name "unconnected-(U3-AF-Pad14)") (class "Default")
      (node (ref "U3") (pin "14") (pinfunction "AF_14") (pintype "bidirectional"))
    )
    (net (code "166") (name "unconnected-(U3-FOUT{slash}IRQ-Pad11)") (class "Default")
      (node (ref "U3") (pin "11") (pinfunction "FOUT/IRQ_11") (pintype "bidirectional"))
    )
    (net (code "167") (name "unconnected-(U3-IRQ2-Pad4)") (class "Default")
      (node (ref "U3") (pin "4") (pinfunction "IRQ2_4") (pintype "bidirectional"))
    )
    (net (code "168") (name "unconnected-(U3-TIRQ-Pad12)") (class "Default")
      (node (ref "U3") (pin "12") (pinfunction "TIRQ_12") (pintype "bidirectional"))
    )
    (net (code "169") (name "unconnected-(U3-XI-Pad16)") (class "Default")
      (node (ref "U3") (pin "16") (pinfunction "XI_16") (pintype "bidirectional"))
    )
    (net (code "170") (name "unconnected-(U3-XO-Pad15)") (class "Default")
      (node (ref "U3") (pin "15") (pinfunction "XO_15") (pintype "bidirectional"))
    )
    (net (code "171") (name "unconnected-(U5-HA-Pad15)") (class "Default")
      (node (ref "U5") (pin "15") (pinfunction "HA_15") (pintype "passive"))
    )
    (net (code "172") (name "unconnected-(U5-HB-Pad12)") (class "Default")
      (node (ref "U5") (pin "12") (pinfunction "HB_12") (pintype "bidirectional"))
    )
    (net (code "173") (name "unconnected-(U8-HA-Pad15)") (class "Default")
      (node (ref "U8") (pin "15") (pinfunction "HA_15") (pintype "passive"))
    )
    (net (code "174") (name "unconnected-(U8-HB-Pad12)") (class "Default")
      (node (ref "U8") (pin "12") (pinfunction "HB_12") (pintype "bidirectional"))
    )
    (net (code "175") (name "unconnected-(U11-HA-Pad15)") (class "Default")
      (node (ref "U11") (pin "15") (pinfunction "HA_15") (pintype "passive"))
    )
    (net (code "176") (name "unconnected-(U11-HB-Pad12)") (class "Default")
      (node (ref "U11") (pin "12") (pinfunction "HB_12") (pintype "bidirectional"))
    )
    (net (code "177") (name "unconnected-(U12-HA-Pad15)") (class "Default")
      (node (ref "U12") (pin "15") (pinfunction "HA_15") (pintype "passive"))
    )
    (net (code "178") (name "unconnected-(U12-HB-Pad12)") (class "Default")
      (node (ref "U12") (pin "12") (pinfunction "HB_12") (pintype "bidirectional"))
    )
  )
)
